# Stingray.net
KiCad netlist of a schematic drawn in Altium Designer
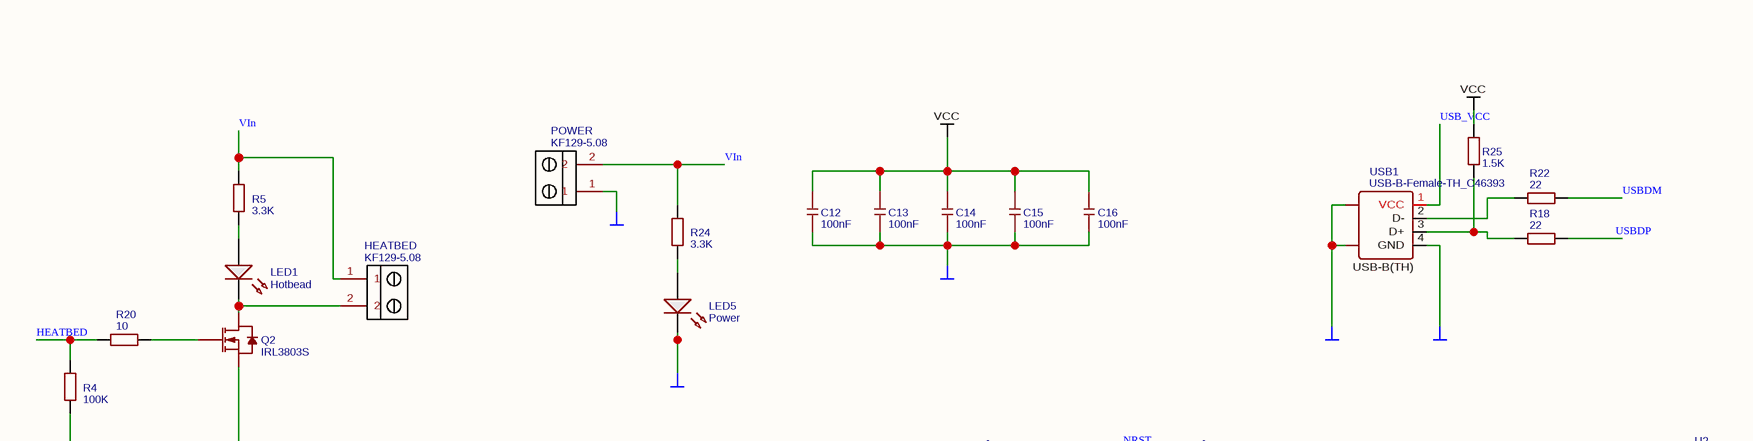
[diagram p0: Stingray.schdoc, top left]
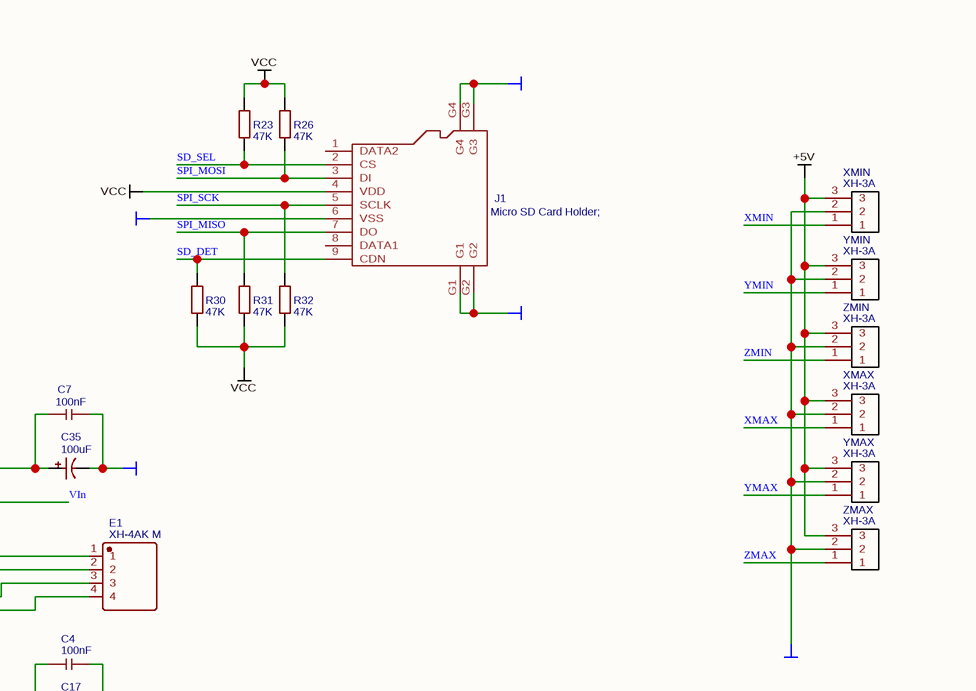
[diagram p1: Stingray.schdoc, top right]
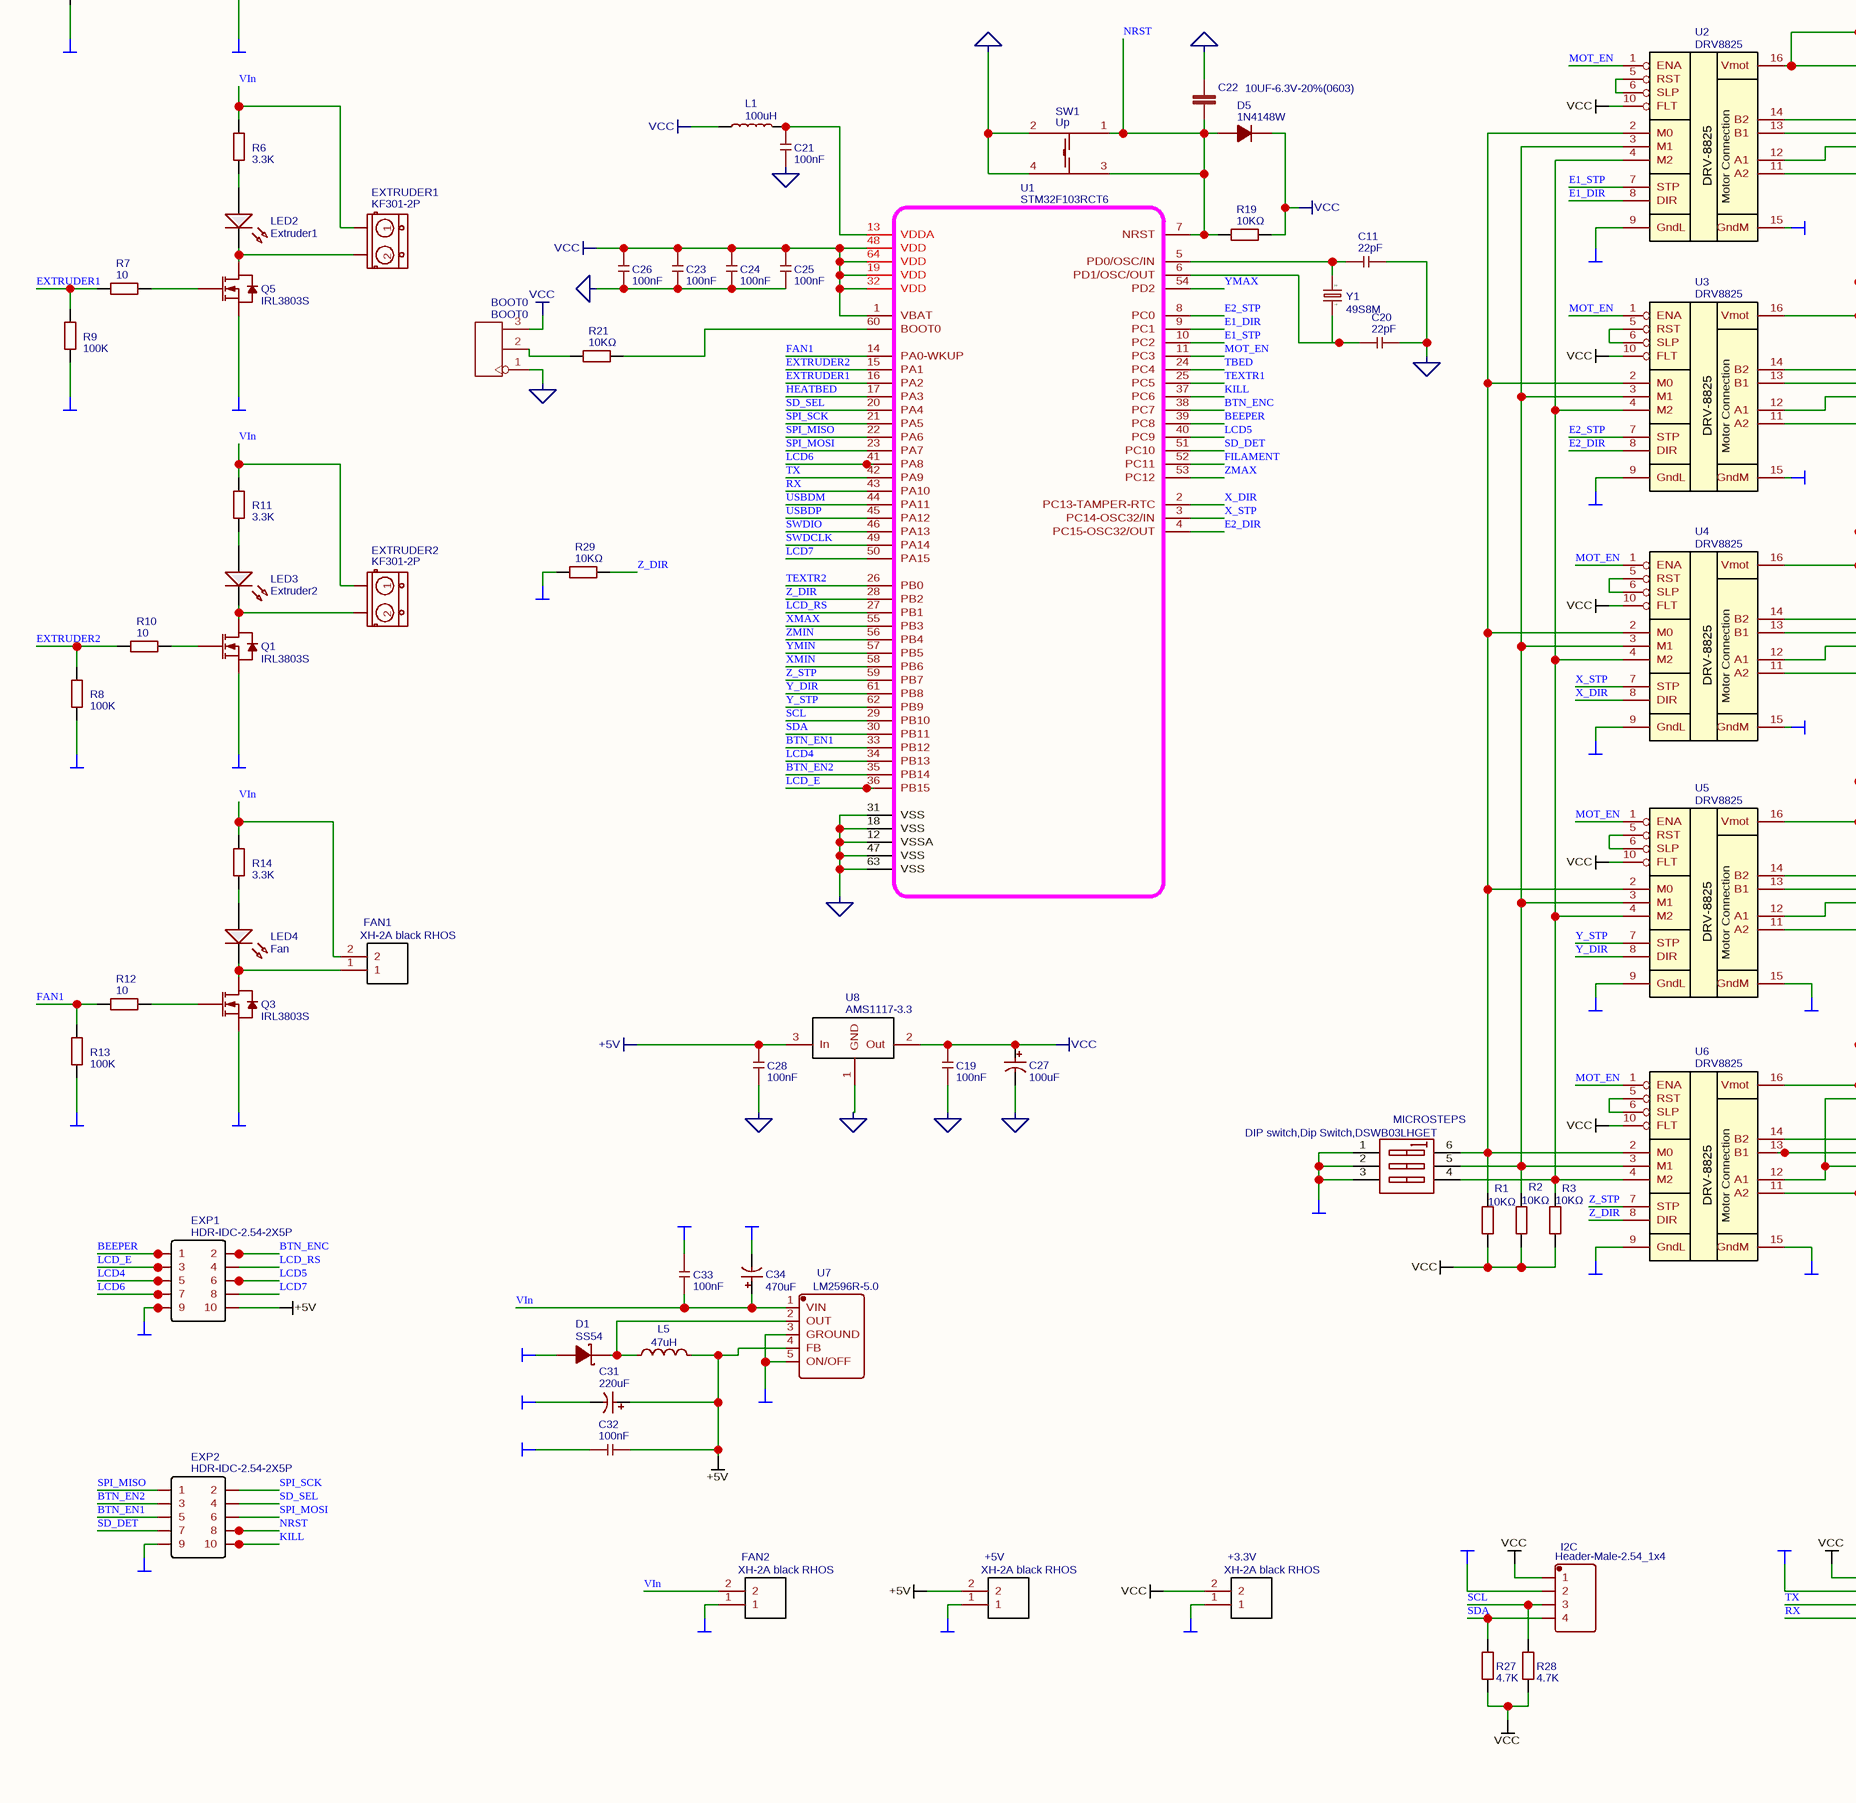
[diagram p2: Stingray.schdoc, bottom left]
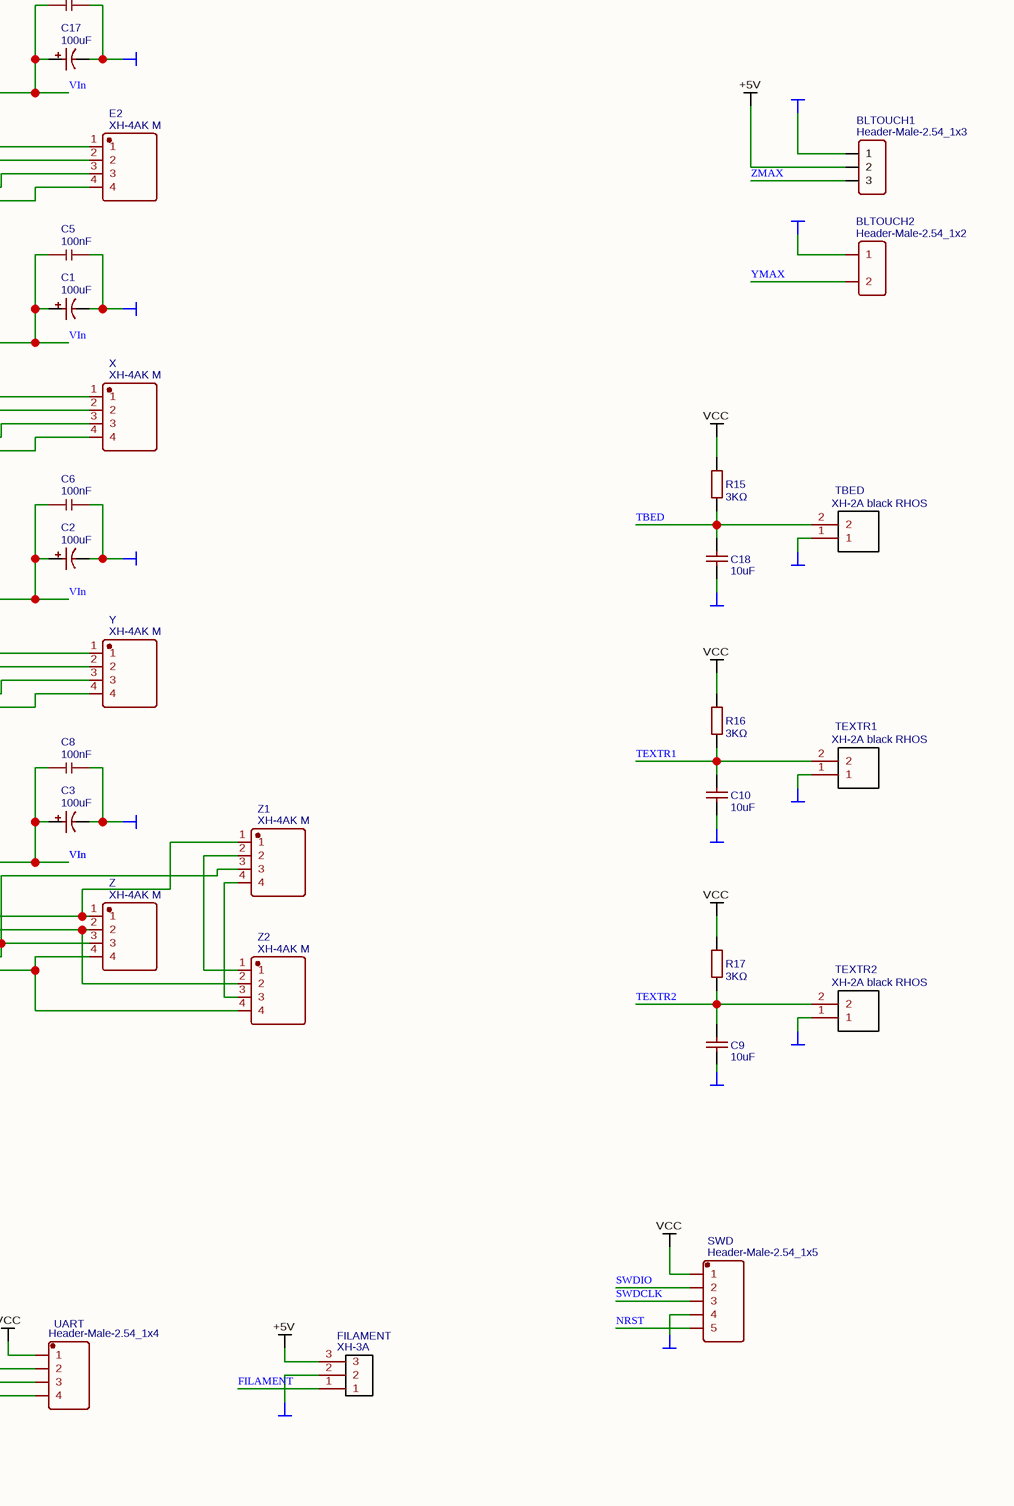
[diagram p3: Stingray.schdoc, bottom right]

(export (version "E")
  (design (tool "Eeschema 10.0.6"))
  (components
    (comp (ref "+3.3V")
      (value "XH-2A black RHOS")
      (fields (field (name "BOM_SUPPLIER PART") "C24193") (field (name "CONTRIBUTOR") "LCSC"))
      (libsource (lib "altium-import") (part "root_2_XH-2A black RHOS_"))
    )
    (comp (ref "+5V")
      (value "XH-2A black RHOS")
      (fields (field (name "BOM_SUPPLIER PART") "C24193") (field (name "CONTRIBUTOR") "LCSC"))
      (libsource (lib "altium-import") (part "root_2_XH-2A black RHOS_"))
    )
    (comp (ref "BLTOUCH1")
      (value "Header-Male-2.54_1x3")
      (fields
        (field (name "BOM_MANUFACTURER PART") "Header2.54mm 1*3P")
        (field (name "BOM_SUPPLIER PART") "C49257")
      )
      (libsource (lib "altium-import") (part "root_0_Header-Male-2.54_1x3_"))
    )
    (comp (ref "BLTOUCH2")
      (value "Header-Male-2.54_1x2")
      (fields (field (name "BOM_MANUFACTURER PART") "826629-2") (field (name "BOM_SUPPLIER PART") "C86471"))
      (libsource (lib "altium-import") (part "root_0_Header-Male-2.54_1x2_"))
    )
    (comp (ref "BOOT0")
      (value "BOOT0")
      (description "DIP-Black-Male-Header-VERT-3P")
      (fields (field (name "BOM_MANUFACTURER PART") "?"))
      (libsource (lib "altium-import") (part "root_2_BOOT0_"))
    )
    (comp (ref "C1")
      (value "100uF")
      (fields
        (field (name "BOM_MANUFACTURER PART") "UT1V101M0607VG")
        (field (name "BOM_SUPPLIER PART") "C82002")
      )
      (libsource (lib "altium-import") (part "root_0_100uF_"))
    )
    (comp (ref "C2")
      (value "100uF")
      (fields
        (field (name "BOM_MANUFACTURER PART") "UT1V101M0607VG")
        (field (name "BOM_SUPPLIER PART") "C82002")
      )
      (libsource (lib "altium-import") (part "root_0_100uF_"))
    )
    (comp (ref "C3")
      (value "100uF")
      (fields
        (field (name "BOM_MANUFACTURER PART") "UT1V101M0607VG")
        (field (name "BOM_SUPPLIER PART") "C82002")
      )
      (libsource (lib "altium-import") (part "root_0_100uF_"))
    )
    (comp (ref "C4")
      (value "100nF")
      (description "SMD CAP Ceramic 100nF-50V-10%-X7R")
      (fields
        (field (name "BOM_MANUFACTURER PART") "0603B104K500NT")
        (field (name "BOM_SUPPLIER PART") "C30926")
      )
      (libsource (lib "altium-import") (part "root_0_100nF_"))
    )
    (comp (ref "C5")
      (value "100nF")
      (description "SMD CAP Ceramic 100nF-50V-10%-X7R")
      (fields
        (field (name "BOM_MANUFACTURER PART") "0603B104K500NT")
        (field (name "BOM_SUPPLIER PART") "C30926")
      )
      (libsource (lib "altium-import") (part "root_0_100nF_"))
    )
    (comp (ref "C6")
      (value "100nF")
      (description "SMD CAP Ceramic 100nF-50V-10%-X7R")
      (fields
        (field (name "BOM_MANUFACTURER PART") "0603B104K500NT")
        (field (name "BOM_SUPPLIER PART") "C30926")
      )
      (libsource (lib "altium-import") (part "root_0_100nF_"))
    )
    (comp (ref "C7")
      (value "100nF")
      (description "SMD CAP Ceramic 100nF-50V-10%-X7R")
      (fields
        (field (name "BOM_MANUFACTURER PART") "0603B104K500NT")
        (field (name "BOM_SUPPLIER PART") "C30926")
      )
      (libsource (lib "altium-import") (part "root_0_100nF_"))
    )
    (comp (ref "C8")
      (value "100nF")
      (description "SMD CAP Ceramic 100nF-50V-10%-X7R")
      (fields
        (field (name "BOM_MANUFACTURER PART") "0603B104K500NT")
        (field (name "BOM_SUPPLIER PART") "C30926")
      )
      (libsource (lib "altium-import") (part "root_0_100nF_"))
    )
    (comp (ref "C9")
      (value "10uF")
      (fields
        (field (name "BOM_MANUFACTURER PART") "CL10A106MO8NQNC")
        (field (name "BOM_SUPPLIER PART") "C92487")
      )
      (libsource (lib "altium-import") (part "root_1_10uF_"))
    )
    (comp (ref "C10")
      (value "10uF")
      (fields
        (field (name "BOM_MANUFACTURER PART") "CL10A106MO8NQNC")
        (field (name "BOM_SUPPLIER PART") "C92487")
      )
      (libsource (lib "altium-import") (part "root_1_10uF_"))
    )
    (comp (ref "C11")
      (value "22pF")
      (description "SMD CAP Ceramic 15pF-50V-5%-NPO;0603")
      (fields (field (name "BOM_MANUFACTURER PART") "CC0603JRNPO9BN150"))
      (libsource (lib "altium-import") (part "root_0_22pF_"))
    )
    (comp (ref "C12")
      (value "100nF")
      (description "SMD CAP Ceramic 100nF-50V-10%-X7R")
      (fields
        (field (name "BOM_MANUFACTURER PART") "0603B104K500NT")
        (field (name "BOM_SUPPLIER PART") "C30926")
      )
      (libsource (lib "altium-import") (part "root_3_100nF_"))
    )
    (comp (ref "C13")
      (value "100nF")
      (description "SMD CAP Ceramic 100nF-50V-10%-X7R")
      (fields
        (field (name "BOM_MANUFACTURER PART") "0603B104K500NT")
        (field (name "BOM_SUPPLIER PART") "C30926")
      )
      (libsource (lib "altium-import") (part "root_3_100nF_"))
    )
    (comp (ref "C14")
      (value "100nF")
      (description "SMD CAP Ceramic 100nF-50V-10%-X7R")
      (fields
        (field (name "BOM_MANUFACTURER PART") "0603B104K500NT")
        (field (name "BOM_SUPPLIER PART") "C30926")
      )
      (libsource (lib "altium-import") (part "root_3_100nF_"))
    )
    (comp (ref "C15")
      (value "100nF")
      (description "SMD CAP Ceramic 100nF-50V-10%-X7R")
      (fields
        (field (name "BOM_MANUFACTURER PART") "0603B104K500NT")
        (field (name "BOM_SUPPLIER PART") "C30926")
      )
      (libsource (lib "altium-import") (part "root_3_100nF_"))
    )
    (comp (ref "C16")
      (value "100nF")
      (description "SMD CAP Ceramic 100nF-50V-10%-X7R")
      (fields
        (field (name "BOM_MANUFACTURER PART") "0603B104K500NT")
        (field (name "BOM_SUPPLIER PART") "C30926")
      )
      (libsource (lib "altium-import") (part "root_3_100nF_"))
    )
    (comp (ref "C17")
      (value "100uF")
      (fields
        (field (name "BOM_MANUFACTURER PART") "UT1V101M0607VG")
        (field (name "BOM_SUPPLIER PART") "C82002")
      )
      (libsource (lib "altium-import") (part "root_0_100uF_"))
    )
    (comp (ref "C18")
      (value "10uF")
      (fields
        (field (name "BOM_MANUFACTURER PART") "CL10A106MO8NQNC")
        (field (name "BOM_SUPPLIER PART") "C92487")
      )
      (libsource (lib "altium-import") (part "root_1_10uF_"))
    )
    (comp (ref "C19")
      (value "100nF")
      (description "SMD CAP Ceramic 100nF-50V-10%-X7R")
      (fields (field (name "BOM_MANUFACTURER PART") "CC0603KRX7R9BB104"))
      (libsource (lib "altium-import") (part "root_1_100nF_"))
    )
    (comp (ref "C20")
      (value "22pF")
      (description "SMD CAP Ceramic 15pF-50V-5%-NPO;0603")
      (fields (field (name "BOM_MANUFACTURER PART") "CC0603JRNPO9BN150"))
      (libsource (lib "altium-import") (part "root_0_22pF_"))
    )
    (comp (ref "C21")
      (value "100nF")
      (description "SMD CAP Ceramic 100nF-50V-10%-X7R")
      (fields (field (name "BOM_MANUFACTURER PART") "CC0603KRX7R9BB104"))
      (libsource (lib "altium-import") (part "root_3_100nF_"))
    )
    (comp (ref "C22")
      (value "10UF-6.3V-20%(0603)")
      (fields (field (name "BOM_MANUFACTURER PART") "?") (field (name "CONTRIBUTOR") "SparkFun"))
      (libsource (lib "altium-import") (part "root_0_10UF-6.3V-20%(0603)_"))
    )
    (comp (ref "C23")
      (value "100nF")
      (description "SMD CAP Ceramic 100nF-50V-10%-X7R")
      (fields (field (name "BOM_MANUFACTURER PART") "CC0603KRX7R9BB104"))
      (libsource (lib "altium-import") (part "root_3_100nF_"))
    )
    (comp (ref "C24")
      (value "100nF")
      (description "SMD CAP Ceramic 100nF-50V-10%-X7R")
      (fields (field (name "BOM_MANUFACTURER PART") "CC0603KRX7R9BB104"))
      (libsource (lib "altium-import") (part "root_3_100nF_"))
    )
    (comp (ref "C25")
      (value "100nF")
      (description "SMD CAP Ceramic 100nF-50V-10%-X7R")
      (fields (field (name "BOM_MANUFACTURER PART") "CC0603KRX7R9BB104"))
      (libsource (lib "altium-import") (part "root_3_100nF_"))
    )
    (comp (ref "C26")
      (value "100nF")
      (description "SMD CAP Ceramic 100nF-50V-10%-X7R")
      (fields (field (name "BOM_MANUFACTURER PART") "CC0603KRX7R9BB104"))
      (libsource (lib "altium-import") (part "root_3_100nF_"))
    )
    (comp (ref "C27")
      (value "100uF")
      (fields
        (field (name "BOM_MANUFACTURER PART") "MV101M6R3E055A")
        (field (name "BOM_SUPPLIER PART") "C65207")
      )
      (libsource (lib "altium-import") (part "root_3_100uF_"))
    )
    (comp (ref "C28")
      (value "100nF")
      (description "SMD CAP Ceramic 100nF-50V-10%-X7R")
      (fields (field (name "BOM_MANUFACTURER PART") "CC0603KRX7R9BB104"))
      (libsource (lib "altium-import") (part "root_3_100nF_"))
    )
    (comp (ref "C31")
      (value "220uF")
      (fields
        (field (name "BOM_MANUFACTURER PART") "UT1A221M0605VG")
        (field (name "BOM_SUPPLIER PART") "C81994")
      )
      (libsource (lib "altium-import") (part "root_2_220uF_"))
    )
    (comp (ref "C32")
      (value "100nF")
      (description "SMD CAP Ceramic 100nF-50V-10%-X7R")
      (fields (field (name "BOM_MANUFACTURER PART") "CC0603KRX7R9BB104"))
      (libsource (lib "altium-import") (part "root_2_100nF_"))
    )
    (comp (ref "C33")
      (value "100nF")
      (description "SMD CAP Ceramic 100nF-50V-10%-X7R")
      (fields (field (name "BOM_MANUFACTURER PART") "CC0603KRX7R9BB104"))
      (libsource (lib "altium-import") (part "root_3_100nF_"))
    )
    (comp (ref "C34")
      (value "470uF")
      (fields
        (field (name "BOM_MANUFACTURER PART") "RVT1V681M1213")
        (field (name "BOM_SUPPLIER PART") "C98216")
      )
      (libsource (lib "altium-import") (part "root_1_470uF_"))
    )
    (comp (ref "C35")
      (value "100uF")
      (fields
        (field (name "BOM_MANUFACTURER PART") "UT1V101M0607VG")
        (field (name "BOM_SUPPLIER PART") "C82002")
      )
      (libsource (lib "altium-import") (part "root_0_100uF_"))
    )
    (comp (ref "D1")
      (value "SS54")
      (fields (field (name "BOM_SUPPLIER PART") "C32513"))
      (libsource (lib "altium-import") (part "root_0_SS54_"))
    )
    (comp (ref "D5")
      (value "1N4148W")
      (fields (field (name "BOM_SUPPLIER PART") "C89641"))
      (libsource (lib "altium-import") (part "root_0_1N4148W_"))
    )
    (comp (ref "E1")
      (value "XH-4AK M")
      (fields (field (name "BOM_SUPPLIER PART") "C146106") (field (name "CONTRIBUTOR") "LCSC"))
      (libsource (lib "altium-import") (part "root_0_XH-4AK M_"))
    )
    (comp (ref "E2")
      (value "XH-4AK M")
      (fields (field (name "BOM_SUPPLIER PART") "C146106") (field (name "CONTRIBUTOR") "LCSC"))
      (libsource (lib "altium-import") (part "root_0_XH-4AK M_"))
    )
    (comp (ref "EXP1")
      (value "HDR-IDC-2.54-2X5P")
      (fields
        (field (name "BOM_MANUFACTURER PART") "IDC Box 2.54mm 2X5P")
        (field (name "BOM_SUPPLIER PART") "C5665")
      )
      (libsource (lib "altium-import") (part "root_0_HDR-IDC-2.54-2X5P_"))
    )
    (comp (ref "EXP2")
      (value "HDR-IDC-2.54-2X5P")
      (fields
        (field (name "BOM_MANUFACTURER PART") "IDC Box 2.54mm 2X5P")
        (field (name "BOM_SUPPLIER PART") "C5665")
      )
      (libsource (lib "altium-import") (part "root_0_HDR-IDC-2.54-2X5P_"))
    )
    (comp (ref "EXTRUDER1")
      (value "KF301-2P")
      (fields (field (name "BOM_MANUFACTURER PART") "?") (field (name "CONTRIBUTOR") "vonk0031"))
      (libsource (lib "altium-import") (part "root_3_KF301-2P_"))
    )
    (comp (ref "EXTRUDER2")
      (value "KF301-2P")
      (fields (field (name "BOM_MANUFACTURER PART") "?") (field (name "CONTRIBUTOR") "vonk0031"))
      (libsource (lib "altium-import") (part "root_3_KF301-2P_"))
    )
    (comp (ref "FAN1")
      (value "XH-2A black RHOS")
      (fields (field (name "BOM_SUPPLIER PART") "C24193") (field (name "CONTRIBUTOR") "LCSC"))
      (libsource (lib "altium-import") (part "root_2_XH-2A black RHOS_"))
    )
    (comp (ref "FAN2")
      (value "XH-2A black RHOS")
      (fields (field (name "BOM_SUPPLIER PART") "C24193") (field (name "CONTRIBUTOR") "LCSC"))
      (libsource (lib "altium-import") (part "root_2_XH-2A black RHOS_"))
    )
    (comp (ref "FILAMENT")
      (value "XH-3A")
      (fields (field (name "BOM_SUPPLIER PART") "C2316") (field (name "CONTRIBUTOR") "LCSC"))
      (libsource (lib "altium-import") (part "root_2_XH-3A_"))
    )
    (comp (ref "HEATBED")
      (value "KF129-5.08")
      (fields (field (name "CONTRIBUTOR") "mmaygli"))
      (libsource (lib "altium-import") (part "root_0_KF129-5.08_"))
    )
    (comp (ref "I2C")
      (value "Header-Male-2.54_1x4")
      (fields
        (field (name "BOM_MANUFACTURER PART") "210S-1*4P L=11.6MMGold-plated black")
        (field (name "BOM_SUPPLIER PART") "C124378")
        (field (name "CONTRIBUTOR") "LCSC")
      )
      (libsource (lib "altium-import") (part "root_0_Header-Male-2.54_1x4_"))
    )
    (comp (ref "J1")
      (value "Micro SD Card Holder;")
      (fields (field (name "BOM_MANUFACTURER PART") "?"))
      (libsource (lib "altium-import") (part "root_0_Micro SD Card Holder;_"))
    )
    (comp (ref "L1")
      (value "100uH")
      (fields
        (field (name "TOLERANCE") "±10%")
        (field (name "BOM_MANUFACTURER PART") "LGA0410-102KP52E")
        (field (name "BOM_SUPPLIER PART") "C72360")
      )
      (libsource (lib "altium-import") (part "root_0_100uH_"))
    )
    (comp (ref "L5")
      (value "47uH")
      (fields
        (field (name "BOM_SUPPLIER PART") "C253613")
        (field (name "BOM_MANUFACTURER PART") "ABG10A50M470")
        (field (name "CONTRIBUTOR") "LCSC")
      )
      (libsource (lib "altium-import") (part "root_0_47uH_"))
    )
    (comp (ref "LED1")
      (value "Hotbead")
      (fields
        (field (name "BOM_MANUFACTURER PART") "17-21/GHC-YR1S2/3T")
        (field (name "BOM_SUPPLIER PART") "E73546")
      )
      (libsource (lib "altium-import") (part "root_3_Hotbead_"))
    )
    (comp (ref "LED2")
      (value "Extruder1")
      (fields
        (field (name "BOM_MANUFACTURER PART") "17-21/GHC-YR1S2/3T")
        (field (name "BOM_SUPPLIER PART") "E73546")
      )
      (libsource (lib "altium-import") (part "root_3_Extruder1_"))
    )
    (comp (ref "LED3")
      (value "Extruder2")
      (fields
        (field (name "BOM_MANUFACTURER PART") "17-21/GHC-YR1S2/3T")
        (field (name "BOM_SUPPLIER PART") "E73546")
      )
      (libsource (lib "altium-import") (part "root_3_Extruder2_"))
    )
    (comp (ref "LED4")
      (value "Fan")
      (fields
        (field (name "BOM_MANUFACTURER PART") "17-21/GHC-YR1S2/3T")
        (field (name "BOM_SUPPLIER PART") "E73546")
      )
      (libsource (lib "altium-import") (part "root_3_Fan_"))
    )
    (comp (ref "LED5")
      (value "Power")
      (fields
        (field (name "BOM_MANUFACTURER PART") "17-21/GHC-YR1S2/3T")
        (field (name "BOM_SUPPLIER PART") "E73546")
      )
      (libsource (lib "altium-import") (part "root_3_Power_"))
    )
    (comp (ref "MICROSTEPS")
      (value "DIP switch,Dip Switch,DSWB03LHGET")
      (fields (field (name "BOM_SUPPLIER PART") "C99420") (field (name "CONTRIBUTOR") "LCSC"))
      (libsource (lib "altium-import") (part "root_0_DIP switch,Dip Switch,DSWB03LHGET_"))
    )
    (comp (ref "POWER")
      (value "KF129-5.08")
      (fields (field (name "CONTRIBUTOR") "mmaygli"))
      (libsource (lib "altium-import") (part "root_2_KF129-5.08_"))
    )
    (comp (ref "Q1")
      (value "IRL3803S")
      (fields (field (name "BOM_SUPPLIER PART") "C2669"))
      (libsource (lib "altium-import") (part "root_0_IRL3803S_"))
    )
    (comp (ref "Q2")
      (value "IRL3803S")
      (fields (field (name "BOM_SUPPLIER PART") "C2669"))
      (libsource (lib "altium-import") (part "root_0_IRL3803S_"))
    )
    (comp (ref "Q3")
      (value "IRL3803S")
      (fields (field (name "BOM_SUPPLIER PART") "C2669"))
      (libsource (lib "altium-import") (part "root_0_IRL3803S_"))
    )
    (comp (ref "Q5")
      (value "IRL3803S")
      (fields (field (name "BOM_SUPPLIER PART") "C2669"))
      (libsource (lib "altium-import") (part "root_0_IRL3803S_"))
    )
    (comp (ref "R1")
      (value "10KΩ")
      (fields
        (field (name "POWER") "1/10W")
        (field (name "TOLERANCE") "±1%")
        (field (name "BOM_MANUFACTURER PART") "0603WAF1002T5E")
      )
      (libsource (lib "altium-import") (part "root_3_10KΩ_"))
    )
    (comp (ref "R2")
      (value "10KΩ")
      (fields
        (field (name "POWER") "1/10W")
        (field (name "TOLERANCE") "±1%")
        (field (name "BOM_MANUFACTURER PART") "0603WAF1002T5E")
      )
      (libsource (lib "altium-import") (part "root_3_10KΩ_"))
    )
    (comp (ref "R3")
      (value "10KΩ")
      (fields
        (field (name "POWER") "1/10W")
        (field (name "TOLERANCE") "±1%")
        (field (name "BOM_MANUFACTURER PART") "0603WAF1002T5E")
      )
      (libsource (lib "altium-import") (part "root_3_10KΩ_"))
    )
    (comp (ref "R4")
      (value "100K")
      (fields
        (field (name "POWER") "1/10W")
        (field (name "TOLERANCE") "±1%")
        (field (name "BOM_MANUFACTURER PART") "0603WAF1002T5E")
      )
      (libsource (lib "altium-import") (part "root_3_100K_"))
    )
    (comp (ref "R5")
      (value "3.3K")
      (fields
        (field (name "POWER") "1/10W")
        (field (name "TOLERANCE") "±1%")
        (field (name "BOM_MANUFACTURER PART") "0603WAF1002T5E")
      )
      (libsource (lib "altium-import") (part "root_3_3.3K_"))
    )
    (comp (ref "R6")
      (value "3.3K")
      (fields
        (field (name "POWER") "1/10W")
        (field (name "TOLERANCE") "±1%")
        (field (name "BOM_MANUFACTURER PART") "0603WAF1002T5E")
      )
      (libsource (lib "altium-import") (part "root_3_3.3K_"))
    )
    (comp (ref "R7")
      (value "10")
      (fields
        (field (name "POWER") "1/10W")
        (field (name "TOLERANCE") "±1%")
        (field (name "BOM_MANUFACTURER PART") "0603WAF1002T5E")
      )
      (libsource (lib "altium-import") (part "root_2_10_"))
    )
    (comp (ref "R8")
      (value "100K")
      (fields
        (field (name "POWER") "1/10W")
        (field (name "TOLERANCE") "±1%")
        (field (name "BOM_MANUFACTURER PART") "0603WAF1002T5E")
      )
      (libsource (lib "altium-import") (part "root_3_100K_"))
    )
    (comp (ref "R9")
      (value "100K")
      (fields
        (field (name "POWER") "1/10W")
        (field (name "TOLERANCE") "±1%")
        (field (name "BOM_MANUFACTURER PART") "0603WAF1002T5E")
      )
      (libsource (lib "altium-import") (part "root_3_100K_"))
    )
    (comp (ref "R10")
      (value "10")
      (fields
        (field (name "POWER") "1/10W")
        (field (name "TOLERANCE") "±1%")
        (field (name "BOM_MANUFACTURER PART") "0603WAF1002T5E")
      )
      (libsource (lib "altium-import") (part "root_2_10_"))
    )
    (comp (ref "R11")
      (value "3.3K")
      (fields
        (field (name "POWER") "1/10W")
        (field (name "TOLERANCE") "±1%")
        (field (name "BOM_MANUFACTURER PART") "0603WAF1002T5E")
      )
      (libsource (lib "altium-import") (part "root_3_3.3K_"))
    )
    (comp (ref "R12")
      (value "10")
      (fields
        (field (name "POWER") "1/10W")
        (field (name "TOLERANCE") "±1%")
        (field (name "BOM_MANUFACTURER PART") "0603WAF1002T5E")
      )
      (libsource (lib "altium-import") (part "root_2_10_"))
    )
    (comp (ref "R13")
      (value "100K")
      (fields
        (field (name "POWER") "1/10W")
        (field (name "TOLERANCE") "±1%")
        (field (name "BOM_MANUFACTURER PART") "0603WAF1002T5E")
      )
      (libsource (lib "altium-import") (part "root_3_100K_"))
    )
    (comp (ref "R14")
      (value "3.3K")
      (fields
        (field (name "POWER") "1/10W")
        (field (name "TOLERANCE") "±1%")
        (field (name "BOM_MANUFACTURER PART") "0603WAF1002T5E")
      )
      (libsource (lib "altium-import") (part "root_3_3.3K_"))
    )
    (comp (ref "R15")
      (value "3KΩ")
      (fields
        (field (name "BOM_MANUFACTURER PART") "RK73B1JTTD302J")
        (field (name "BOM_SUPPLIER PART") "C131708")
        (field (name "CONTRIBUTOR") "LCSC")
      )
      (libsource (lib "altium-import") (part "root_1_3KΩ_"))
    )
    (comp (ref "R16")
      (value "3KΩ")
      (fields
        (field (name "BOM_MANUFACTURER PART") "RK73B1JTTD302J")
        (field (name "BOM_SUPPLIER PART") "C131708")
        (field (name "CONTRIBUTOR") "LCSC")
      )
      (libsource (lib "altium-import") (part "root_1_3KΩ_"))
    )
    (comp (ref "R17")
      (value "3KΩ")
      (fields
        (field (name "BOM_MANUFACTURER PART") "RK73B1JTTD302J")
        (field (name "BOM_SUPPLIER PART") "C131708")
        (field (name "CONTRIBUTOR") "LCSC")
      )
      (libsource (lib "altium-import") (part "root_1_3KΩ_"))
    )
    (comp (ref "R18")
      (value "22")
      (fields
        (field (name "POWER") "1/10W")
        (field (name "TOLERANCE") "±1%")
        (field (name "BOM_MANUFACTURER PART") "0603WAF1002T5E")
      )
      (libsource (lib "altium-import") (part "root_2_22_"))
    )
    (comp (ref "R19")
      (value "10KΩ")
      (fields
        (field (name "POWER") "1/10W")
        (field (name "TOLERANCE") "±1%")
        (field (name "BOM_MANUFACTURER PART") "0603WAF1002T5E")
      )
      (libsource (lib "altium-import") (part "root_0_10KΩ_"))
    )
    (comp (ref "R20")
      (value "10")
      (fields
        (field (name "POWER") "1/10W")
        (field (name "TOLERANCE") "±1%")
        (field (name "BOM_MANUFACTURER PART") "0603WAF1002T5E")
      )
      (libsource (lib "altium-import") (part "root_2_10_"))
    )
    (comp (ref "R21")
      (value "10KΩ")
      (fields
        (field (name "POWER") "1/10W")
        (field (name "TOLERANCE") "±1%")
        (field (name "BOM_MANUFACTURER PART") "0603WAF1002T5E")
      )
      (libsource (lib "altium-import") (part "root_2_10KΩ_"))
    )
    (comp (ref "R22")
      (value "22")
      (fields
        (field (name "POWER") "1/10W")
        (field (name "TOLERANCE") "±1%")
        (field (name "BOM_MANUFACTURER PART") "0603WAF1002T5E")
      )
      (libsource (lib "altium-import") (part "root_2_22_"))
    )
    (comp (ref "R23")
      (value "47K")
      (fields
        (field (name "POWER") "1/10W")
        (field (name "TOLERANCE") "±1%")
        (field (name "BOM_MANUFACTURER PART") "0603WAF1002T5E")
      )
      (libsource (lib "altium-import") (part "root_3_47K_"))
    )
    (comp (ref "R24")
      (value "3.3K")
      (fields
        (field (name "POWER") "1/10W")
        (field (name "TOLERANCE") "±1%")
        (field (name "BOM_MANUFACTURER PART") "0603WAF1002T5E")
      )
      (libsource (lib "altium-import") (part "root_3_3.3K_"))
    )
    (comp (ref "R25")
      (value "1.5K")
      (fields
        (field (name "POWER") "1/10W")
        (field (name "TOLERANCE") "±1%")
        (field (name "BOM_MANUFACTURER PART") "0603WAF1002T5E")
      )
      (libsource (lib "altium-import") (part "root_3_1.5K_"))
    )
    (comp (ref "R26")
      (value "47K")
      (fields
        (field (name "POWER") "1/10W")
        (field (name "TOLERANCE") "±1%")
        (field (name "BOM_MANUFACTURER PART") "0603WAF1002T5E")
      )
      (libsource (lib "altium-import") (part "root_3_47K_"))
    )
    (comp (ref "R27")
      (value "4.7K")
      (fields
        (field (name "POWER") "1/10W")
        (field (name "TOLERANCE") "±1%")
        (field (name "BOM_MANUFACTURER PART") "0603WAF1002T5E")
      )
      (libsource (lib "altium-import") (part "root_3_4.7K_"))
    )
    (comp (ref "R28")
      (value "4.7K")
      (fields
        (field (name "POWER") "1/10W")
        (field (name "TOLERANCE") "±1%")
        (field (name "BOM_MANUFACTURER PART") "0603WAF1002T5E")
      )
      (libsource (lib "altium-import") (part "root_3_4.7K_"))
    )
    (comp (ref "R29")
      (value "10KΩ")
      (fields
        (field (name "POWER") "1/10W")
        (field (name "TOLERANCE") "±1%")
        (field (name "BOM_MANUFACTURER PART") "0603WAF1002T5E")
      )
      (libsource (lib "altium-import") (part "root_2_10KΩ_"))
    )
    (comp (ref "R30")
      (value "47K")
      (fields
        (field (name "POWER") "1/10W")
        (field (name "TOLERANCE") "±1%")
        (field (name "BOM_MANUFACTURER PART") "0603WAF1002T5E")
      )
      (libsource (lib "altium-import") (part "root_3_47K_"))
    )
    (comp (ref "R31")
      (value "47K")
      (fields
        (field (name "POWER") "1/10W")
        (field (name "TOLERANCE") "±1%")
        (field (name "BOM_MANUFACTURER PART") "0603WAF1002T5E")
      )
      (libsource (lib "altium-import") (part "root_3_47K_"))
    )
    (comp (ref "R32")
      (value "47K")
      (fields
        (field (name "POWER") "1/10W")
        (field (name "TOLERANCE") "±1%")
        (field (name "BOM_MANUFACTURER PART") "0603WAF1002T5E")
      )
      (libsource (lib "altium-import") (part "root_3_47K_"))
    )
    (comp (ref "SW1")
      (value "Up")
      (fields
        (field (name "BOM_MANUFACTURER PART") "Switch,6*6*5Plastic head,260G, 0.25mm,DIP2")
        (field (name "BOM_SUPPLIER PART") "C71845")
        (field (name "CONTRIBUTOR") "LCSC")
      )
      (libsource (lib "altium-import") (part "root_0_Up_"))
    )
    (comp (ref "SWD")
      (value "Header-Male-2.54_1x5")
      (fields
        (field (name "BOM_MANUFACTURER PART") "210S-1*5P L=11.6MMGold-plated black")
        (field (name "BOM_SUPPLIER PART") "C124379")
        (field (name "CONTRIBUTOR") "LCSC")
      )
      (libsource (lib "altium-import") (part "root_0_Header-Male-2.54_1x5_"))
    )
    (comp (ref "TBED")
      (value "XH-2A black RHOS")
      (fields (field (name "BOM_SUPPLIER PART") "C24193") (field (name "CONTRIBUTOR") "LCSC"))
      (libsource (lib "altium-import") (part "root_2_XH-2A black RHOS_"))
    )
    (comp (ref "TEXTR1")
      (value "XH-2A black RHOS")
      (fields (field (name "BOM_SUPPLIER PART") "C24193") (field (name "CONTRIBUTOR") "LCSC"))
      (libsource (lib "altium-import") (part "root_2_XH-2A black RHOS_"))
    )
    (comp (ref "TEXTR2")
      (value "XH-2A black RHOS")
      (fields (field (name "BOM_SUPPLIER PART") "C24193") (field (name "CONTRIBUTOR") "LCSC"))
      (libsource (lib "altium-import") (part "root_2_XH-2A black RHOS_"))
    )
    (comp (ref "U1")
      (value "STM32F103RCT6")
      (fields (field (name "BOM_MANUFACTURER PART") "?"))
      (libsource (lib "altium-import") (part "root_0_STM32F103RCT6_"))
    )
    (comp (ref "U2")
      (value "DRV8825")
      (fields (field (name "BOM_SUPPLIER PART") "2133") (field (name "CONTRIBUTOR") "Origami30"))
      (libsource (lib "altium-import") (part "root_0_DRV8825_"))
    )
    (comp (ref "U3")
      (value "DRV8825")
      (fields (field (name "BOM_SUPPLIER PART") "2133") (field (name "CONTRIBUTOR") "Origami30"))
      (libsource (lib "altium-import") (part "root_0_DRV8825_"))
    )
    (comp (ref "U4")
      (value "DRV8825")
      (fields (field (name "BOM_SUPPLIER PART") "2133") (field (name "CONTRIBUTOR") "Origami30"))
      (libsource (lib "altium-import") (part "root_0_DRV8825_"))
    )
    (comp (ref "U5")
      (value "DRV8825")
      (fields (field (name "BOM_SUPPLIER PART") "2133") (field (name "CONTRIBUTOR") "Origami30"))
      (libsource (lib "altium-import") (part "root_0_DRV8825_"))
    )
    (comp (ref "U6")
      (value "DRV8825")
      (fields (field (name "BOM_SUPPLIER PART") "2133") (field (name "CONTRIBUTOR") "Origami30"))
      (libsource (lib "altium-import") (part "root_0_DRV8825_"))
    )
    (comp (ref "U7")
      (value "LM2596R-5.0")
      (fields (field (name "BOM_SUPPLIER PART") "C77782"))
      (libsource (lib "altium-import") (part "root_0_LM2596R-5.0_"))
    )
    (comp (ref "U8")
      (value "AMS1117-3.3")
      (fields (field (name "BOM_SUPPLIER PART") "C6186"))
      (libsource (lib "altium-import") (part "root_0_AMS1117-3.3_"))
    )
    (comp (ref "UART")
      (value "Header-Male-2.54_1x4")
      (fields
        (field (name "BOM_MANUFACTURER PART") "210S-1*4P L=11.6MMGold-plated black")
        (field (name "BOM_SUPPLIER PART") "C124378")
        (field (name "CONTRIBUTOR") "LCSC")
      )
      (libsource (lib "altium-import") (part "root_0_Header-Male-2.54_1x4_"))
    )
    (comp (ref "USB1")
      (value "USB-B-Female-TH_C46393")
      (fields
        (field (name "BOM_MANUFACTURER PART") "USB-B-Female-90-TH")
        (field (name "BOM_SUPPLIER PART") "C46393")
      )
      (libsource (lib "altium-import") (part "root_0_USB-B-Female-TH_C46393_"))
    )
    (comp (ref "X")
      (value "XH-4AK M")
      (fields (field (name "BOM_SUPPLIER PART") "C146106") (field (name "CONTRIBUTOR") "LCSC"))
      (libsource (lib "altium-import") (part "root_0_XH-4AK M_"))
    )
    (comp (ref "XMAX")
      (value "XH-3A")
      (fields (field (name "BOM_SUPPLIER PART") "C2316") (field (name "CONTRIBUTOR") "LCSC"))
      (libsource (lib "altium-import") (part "root_2_XH-3A_"))
    )
    (comp (ref "XMIN")
      (value "XH-3A")
      (fields (field (name "BOM_SUPPLIER PART") "C2316") (field (name "CONTRIBUTOR") "LCSC"))
      (libsource (lib "altium-import") (part "root_2_XH-3A_"))
    )
    (comp (ref "Y")
      (value "XH-4AK M")
      (fields (field (name "BOM_SUPPLIER PART") "C146106") (field (name "CONTRIBUTOR") "LCSC"))
      (libsource (lib "altium-import") (part "root_0_XH-4AK M_"))
    )
    (comp (ref "Y1")
      (value "49S8M")
      (description "DIP Crystal 8MHz-20pF-20ppm-60R;")
      (libsource (lib "altium-import") (part "root_1_49S8M_"))
    )
    (comp (ref "YMAX")
      (value "XH-3A")
      (fields (field (name "BOM_SUPPLIER PART") "C2316") (field (name "CONTRIBUTOR") "LCSC"))
      (libsource (lib "altium-import") (part "root_2_XH-3A_"))
    )
    (comp (ref "YMIN")
      (value "XH-3A")
      (fields (field (name "BOM_SUPPLIER PART") "C2316") (field (name "CONTRIBUTOR") "LCSC"))
      (libsource (lib "altium-import") (part "root_2_XH-3A_"))
    )
    (comp (ref "Z")
      (value "XH-4AK M")
      (fields (field (name "BOM_SUPPLIER PART") "C146106") (field (name "CONTRIBUTOR") "LCSC"))
      (libsource (lib "altium-import") (part "root_0_XH-4AK M_"))
    )
    (comp (ref "Z1")
      (value "XH-4AK M")
      (fields (field (name "BOM_SUPPLIER PART") "C146106") (field (name "CONTRIBUTOR") "LCSC"))
      (libsource (lib "altium-import") (part "root_0_XH-4AK M_"))
    )
    (comp (ref "Z2")
      (value "XH-4AK M")
      (fields (field (name "BOM_SUPPLIER PART") "C146106") (field (name "CONTRIBUTOR") "LCSC"))
      (libsource (lib "altium-import") (part "root_0_XH-4AK M_"))
    )
    (comp (ref "ZMAX")
      (value "XH-3A")
      (fields (field (name "BOM_SUPPLIER PART") "C2316") (field (name "CONTRIBUTOR") "LCSC"))
      (libsource (lib "altium-import") (part "root_2_XH-3A_"))
    )
    (comp (ref "ZMIN")
      (value "XH-3A")
      (fields (field (name "BOM_SUPPLIER PART") "C2316") (field (name "CONTRIBUTOR") "LCSC"))
      (libsource (lib "altium-import") (part "root_2_XH-3A_"))
    )
  )
  (nets
    (net (code "1") (name "+5V") (class "Default")
      (node (ref "+5V") (pin "2") (pinfunction "2_2") (pintype "passive"))
      (node (ref "BLTOUCH1") (pin "2") (pinfunction "2_2") (pintype "passive"))
      (node (ref "C28") (pin "1") (pinfunction "1_1") (pintype "passive"))
      (node (ref "C31") (pin "1") (pinfunction "1_1") (pintype "passive"))
      (node (ref "C32") (pin "1") (pinfunction "1_1") (pintype "passive"))
      (node (ref "EXP1") (pin "10") (pinfunction "10_10") (pintype "passive"))
      (node (ref "FILAMENT") (pin "3") (pinfunction "3_3") (pintype "passive"))
      (node (ref "L5") (pin "2") (pinfunction "2_2") (pintype "passive"))
      (node (ref "U7") (pin "4") (pinfunction "FB_4") (pintype "passive"))
      (node (ref "U8") (pin "3") (pinfunction "In_3") (pintype "passive"))
      (node (ref "XMAX") (pin "3") (pinfunction "3_3") (pintype "passive"))
      (node (ref "XMIN") (pin "3") (pinfunction "3_3") (pintype "passive"))
      (node (ref "YMAX") (pin "3") (pinfunction "3_3") (pintype "passive"))
      (node (ref "YMIN") (pin "3") (pinfunction "3_3") (pintype "passive"))
      (node (ref "ZMAX") (pin "3") (pinfunction "3_3") (pintype "passive"))
      (node (ref "ZMIN") (pin "3") (pinfunction "3_3") (pintype "passive"))
    )
    (net (code "2") (name "/BEEPER") (class "Default")
      (node (ref "EXP1") (pin "1") (pinfunction "1_1") (pintype "passive"))
      (node (ref "U1") (pin "39") (pinfunction "PC8_39") (pintype "passive"))
    )
    (net (code "3") (name "/BTN_EN1") (class "Default")
      (node (ref "EXP2") (pin "5") (pinfunction "5_5") (pintype "passive"))
      (node (ref "U1") (pin "33") (pinfunction "PB12_33") (pintype "passive"))
    )
    (net (code "4") (name "/BTN_EN2") (class "Default")
      (node (ref "EXP2") (pin "3") (pinfunction "3_3") (pintype "passive"))
      (node (ref "U1") (pin "35") (pinfunction "PB14_35") (pintype "passive"))
    )
    (net (code "5") (name "/BTN_ENC") (class "Default")
      (node (ref "EXP1") (pin "2") (pinfunction "2_2") (pintype "passive"))
      (node (ref "U1") (pin "38") (pinfunction "PC7_38") (pintype "passive"))
    )
    (net (code "6") (name "/E1_DIR") (class "Default")
      (node (ref "U1") (pin "9") (pinfunction "PC1_9") (pintype "passive"))
      (node (ref "U2") (pin "8") (pinfunction "DIR_8") (pintype "passive"))
    )
    (net (code "7") (name "/E1_STP") (class "Default")
      (node (ref "U1") (pin "10") (pinfunction "PC2_10") (pintype "passive"))
      (node (ref "U2") (pin "7") (pinfunction "STP_7") (pintype "passive"))
    )
    (net (code "8") (name "/E2_DIR") (class "Default")
      (node (ref "U1") (pin "4") (pinfunction "PC15-OSC32/OUT_4") (pintype "passive"))
      (node (ref "U3") (pin "8") (pinfunction "DIR_8") (pintype "passive"))
    )
    (net (code "9") (name "/E2_STP") (class "Default")
      (node (ref "U1") (pin "8") (pinfunction "PC0_8") (pintype "passive"))
      (node (ref "U3") (pin "7") (pinfunction "STP_7") (pintype "passive"))
    )
    (net (code "10") (name "/EXTRUDER1") (class "Default")
      (node (ref "R7") (pin "2") (pinfunction "2_2") (pintype "passive"))
      (node (ref "R9") (pin "1") (pinfunction "1_1") (pintype "passive"))
      (node (ref "U1") (pin "16") (pinfunction "PA2_16") (pintype "passive"))
    )
    (net (code "11") (name "/EXTRUDER2") (class "Default")
      (node (ref "R10") (pin "2") (pinfunction "2_2") (pintype "passive"))
      (node (ref "R8") (pin "1") (pinfunction "1_1") (pintype "passive"))
      (node (ref "U1") (pin "15") (pinfunction "PA1_15") (pintype "passive"))
    )
    (net (code "12") (name "/FAN1") (class "Default")
      (node (ref "R12") (pin "2") (pinfunction "2_2") (pintype "passive"))
      (node (ref "R13") (pin "1") (pinfunction "1_1") (pintype "passive"))
      (node (ref "U1") (pin "14") (pinfunction "PA0-WKUP_14") (pintype "passive"))
    )
    (net (code "13") (name "/FILAMENT") (class "Default")
      (node (ref "FILAMENT") (pin "1") (pinfunction "1_1") (pintype "passive"))
      (node (ref "U1") (pin "52") (pinfunction "PC11_52") (pintype "passive"))
    )
    (net (code "14") (name "/HEATBED") (class "Default")
      (node (ref "R20") (pin "2") (pinfunction "2_2") (pintype "passive"))
      (node (ref "R4") (pin "1") (pinfunction "1_1") (pintype "passive"))
      (node (ref "U1") (pin "17") (pinfunction "PA3_17") (pintype "passive"))
    )
    (net (code "15") (name "/KILL") (class "Default")
      (node (ref "EXP2") (pin "10") (pinfunction "10_10") (pintype "passive"))
      (node (ref "U1") (pin "37") (pinfunction "PC6_37") (pintype "passive"))
    )
    (net (code "16") (name "/LCD4") (class "Default")
      (node (ref "EXP1") (pin "5") (pinfunction "5_5") (pintype "passive"))
      (node (ref "U1") (pin "34") (pinfunction "PB13_34") (pintype "passive"))
    )
    (net (code "17") (name "/LCD5") (class "Default")
      (node (ref "EXP1") (pin "6") (pinfunction "6_6") (pintype "passive"))
      (node (ref "U1") (pin "40") (pinfunction "PC9_40") (pintype "passive"))
    )
    (net (code "18") (name "/LCD6") (class "Default")
      (node (ref "EXP1") (pin "7") (pinfunction "7_7") (pintype "passive"))
      (node (ref "U1") (pin "41") (pinfunction "PA8_41") (pintype "passive"))
    )
    (net (code "19") (name "/LCD7") (class "Default")
      (node (ref "EXP1") (pin "8") (pinfunction "8_8") (pintype "passive"))
      (node (ref "U1") (pin "50") (pinfunction "PA15_50") (pintype "passive"))
    )
    (net (code "20") (name "/LCD_E") (class "Default")
      (node (ref "EXP1") (pin "3") (pinfunction "3_3") (pintype "passive"))
      (node (ref "U1") (pin "36") (pinfunction "PB15_36") (pintype "passive"))
    )
    (net (code "21") (name "/LCD_RS") (class "Default")
      (node (ref "EXP1") (pin "4") (pinfunction "4_4") (pintype "passive"))
      (node (ref "U1") (pin "27") (pinfunction "PB1_27") (pintype "passive"))
    )
    (net (code "22") (name "/MOT_EN") (class "Default")
      (node (ref "U1") (pin "11") (pinfunction "PC3_11") (pintype "passive"))
      (node (ref "U2") (pin "1") (pinfunction "ENA_1") (pintype "passive"))
      (node (ref "U3") (pin "1") (pinfunction "ENA_1") (pintype "passive"))
      (node (ref "U4") (pin "1") (pinfunction "ENA_1") (pintype "passive"))
      (node (ref "U5") (pin "1") (pinfunction "ENA_1") (pintype "passive"))
      (node (ref "U6") (pin "1") (pinfunction "ENA_1") (pintype "passive"))
    )
    (net (code "23") (name "/NRST") (class "Default")
      (node (ref "C22") (pin "2") (pinfunction "2_2") (pintype "passive"))
      (node (ref "D5") (pin "1") (pinfunction "A_1") (pintype "passive"))
      (node (ref "EXP2") (pin "8") (pinfunction "8_8") (pintype "passive"))
      (node (ref "R19") (pin "1") (pinfunction "1_1") (pintype "passive"))
      (node (ref "SW1") (pin "1") (pinfunction "1_1") (pintype "passive"))
      (node (ref "SW1") (pin "3") (pinfunction "3_3") (pintype "passive"))
      (node (ref "SWD") (pin "5") (pinfunction "5_5") (pintype "passive"))
      (node (ref "U1") (pin "7") (pinfunction "NRST_7") (pintype "passive"))
    )
    (net (code "24") (name "/RX") (class "Default")
      (node (ref "U1") (pin "43") (pinfunction "PA10_43") (pintype "passive"))
      (node (ref "UART") (pin "4") (pinfunction "4_4") (pintype "passive"))
    )
    (net (code "25") (name "/SCL") (class "Default")
      (node (ref "I2C") (pin "3") (pinfunction "3_3") (pintype "passive"))
      (node (ref "R28") (pin "1") (pinfunction "1_1") (pintype "passive"))
      (node (ref "U1") (pin "29") (pinfunction "PB10_29") (pintype "passive"))
    )
    (net (code "26") (name "/SDA") (class "Default")
      (node (ref "I2C") (pin "4") (pinfunction "4_4") (pintype "passive"))
      (node (ref "R27") (pin "1") (pinfunction "1_1") (pintype "passive"))
      (node (ref "U1") (pin "30") (pinfunction "PB11_30") (pintype "passive"))
    )
    (net (code "27") (name "/SD_DET") (class "Default")
      (node (ref "EXP2") (pin "7") (pinfunction "7_7") (pintype "passive"))
      (node (ref "J1") (pin "9") (pinfunction "CDN_9") (pintype "passive"))
      (node (ref "R30") (pin "1") (pinfunction "1_1") (pintype "passive"))
      (node (ref "U1") (pin "51") (pinfunction "PC10_51") (pintype "passive"))
    )
    (net (code "28") (name "/SD_SEL") (class "Default")
      (node (ref "EXP2") (pin "4") (pinfunction "4_4") (pintype "passive"))
      (node (ref "J1") (pin "2") (pinfunction "CS_2") (pintype "passive"))
      (node (ref "R23") (pin "2") (pinfunction "2_2") (pintype "passive"))
      (node (ref "U1") (pin "20") (pinfunction "PA4_20") (pintype "passive"))
    )
    (net (code "29") (name "/SPI_MISO") (class "Default")
      (node (ref "EXP2") (pin "1") (pinfunction "1_1") (pintype "passive"))
      (node (ref "J1") (pin "7") (pinfunction "DO_7") (pintype "passive"))
      (node (ref "R31") (pin "1") (pinfunction "1_1") (pintype "passive"))
      (node (ref "U1") (pin "22") (pinfunction "PA6_22") (pintype "passive"))
    )
    (net (code "30") (name "/SPI_MOSI") (class "Default")
      (node (ref "EXP2") (pin "6") (pinfunction "6_6") (pintype "passive"))
      (node (ref "J1") (pin "3") (pinfunction "DI_3") (pintype "passive"))
      (node (ref "R26") (pin "2") (pinfunction "2_2") (pintype "passive"))
      (node (ref "U1") (pin "23") (pinfunction "PA7_23") (pintype "passive"))
    )
    (net (code "31") (name "/SPI_SCK") (class "Default")
      (node (ref "EXP2") (pin "2") (pinfunction "2_2") (pintype "passive"))
      (node (ref "J1") (pin "5") (pinfunction "SCLK_5") (pintype "passive"))
      (node (ref "R32") (pin "1") (pinfunction "1_1") (pintype "passive"))
      (node (ref "U1") (pin "21") (pinfunction "PA5_21") (pintype "passive"))
    )
    (net (code "32") (name "/SWDCLK") (class "Default")
      (node (ref "SWD") (pin "3") (pinfunction "3_3") (pintype "passive"))
      (node (ref "U1") (pin "49") (pinfunction "PA14_49") (pintype "passive"))
    )
    (net (code "33") (name "/SWDIO") (class "Default")
      (node (ref "SWD") (pin "2") (pinfunction "2_2") (pintype "passive"))
      (node (ref "U1") (pin "46") (pinfunction "PA13_46") (pintype "passive"))
    )
    (net (code "34") (name "/TBED") (class "Default")
      (node (ref "C18") (pin "2") (pinfunction "2_2") (pintype "passive"))
      (node (ref "R15") (pin "1") (pinfunction "1_1") (pintype "passive"))
      (node (ref "TBED") (pin "2") (pinfunction "2_2") (pintype "passive"))
      (node (ref "U1") (pin "24") (pinfunction "PC4_24") (pintype "passive"))
    )
    (net (code "35") (name "/TEXTR1") (class "Default")
      (node (ref "C10") (pin "2") (pinfunction "2_2") (pintype "passive"))
      (node (ref "R16") (pin "1") (pinfunction "1_1") (pintype "passive"))
      (node (ref "TEXTR1") (pin "2") (pinfunction "2_2") (pintype "passive"))
      (node (ref "U1") (pin "25") (pinfunction "PC5_25") (pintype "passive"))
    )
    (net (code "36") (name "/TEXTR2") (class "Default")
      (node (ref "C9") (pin "2") (pinfunction "2_2") (pintype "passive"))
      (node (ref "R17") (pin "1") (pinfunction "1_1") (pintype "passive"))
      (node (ref "TEXTR2") (pin "2") (pinfunction "2_2") (pintype "passive"))
      (node (ref "U1") (pin "26") (pinfunction "PB0_26") (pintype "passive"))
    )
    (net (code "37") (name "/TX") (class "Default")
      (node (ref "U1") (pin "42") (pinfunction "PA9_42") (pintype "passive"))
      (node (ref "UART") (pin "3") (pinfunction "3_3") (pintype "passive"))
    )
    (net (code "38") (name "/USBDM") (class "Default")
      (node (ref "R22") (pin "1") (pinfunction "1_1") (pintype "passive"))
      (node (ref "U1") (pin "44") (pinfunction "PA11_44") (pintype "passive"))
    )
    (net (code "39") (name "/USBDP") (class "Default")
      (node (ref "R18") (pin "1") (pinfunction "1_1") (pintype "passive"))
      (node (ref "U1") (pin "45") (pinfunction "PA12_45") (pintype "passive"))
    )
    (net (code "40") (name "/USB_VCC") (class "Default")
      (node (ref "USB1") (pin "1") (pinfunction "VCC_1") (pintype "passive"))
    )
    (net (code "41") (name "/VIn") (class "Default")
      (node (ref "C1") (pin "1") (pinfunction "1_1") (pintype "passive"))
      (node (ref "C17") (pin "1") (pinfunction "1_1") (pintype "passive"))
      (node (ref "C2") (pin "1") (pinfunction "1_1") (pintype "passive"))
      (node (ref "C3") (pin "1") (pinfunction "1_1") (pintype "passive"))
      (node (ref "C33") (pin "2") (pinfunction "2_2") (pintype "passive"))
      (node (ref "C34") (pin "1") (pinfunction "1_1") (pintype "passive"))
      (node (ref "C35") (pin "1") (pinfunction "1_1") (pintype "passive"))
      (node (ref "C4") (pin "1") (pinfunction "1_1") (pintype "passive"))
      (node (ref "C5") (pin "1") (pinfunction "1_1") (pintype "passive"))
      (node (ref "C6") (pin "1") (pinfunction "1_1") (pintype "passive"))
      (node (ref "C7") (pin "1") (pinfunction "1_1") (pintype "passive"))
      (node (ref "C8") (pin "1") (pinfunction "1_1") (pintype "passive"))
      (node (ref "EXTRUDER1") (pin "1") (pinfunction "1_1") (pintype "passive"))
      (node (ref "EXTRUDER2") (pin "1") (pinfunction "1_1") (pintype "passive"))
      (node (ref "FAN1") (pin "2") (pinfunction "2_2") (pintype "passive"))
      (node (ref "FAN2") (pin "2") (pinfunction "2_2") (pintype "passive"))
      (node (ref "HEATBED") (pin "1") (pinfunction "1_1") (pintype "passive"))
      (node (ref "POWER") (pin "2") (pinfunction "2_2") (pintype "passive"))
      (node (ref "R11") (pin "1") (pinfunction "1_1") (pintype "passive"))
      (node (ref "R14") (pin "1") (pinfunction "1_1") (pintype "passive"))
      (node (ref "R24") (pin "1") (pinfunction "1_1") (pintype "passive"))
      (node (ref "R5") (pin "1") (pinfunction "1_1") (pintype "passive"))
      (node (ref "R6") (pin "1") (pinfunction "1_1") (pintype "passive"))
      (node (ref "U2") (pin "16") (pinfunction "Vmot_16") (pintype "passive"))
      (node (ref "U3") (pin "16") (pinfunction "Vmot_16") (pintype "passive"))
      (node (ref "U4") (pin "16") (pinfunction "Vmot_16") (pintype "passive"))
      (node (ref "U5") (pin "16") (pinfunction "Vmot_16") (pintype "passive"))
      (node (ref "U6") (pin "16") (pinfunction "Vmot_16") (pintype "passive"))
      (node (ref "U7") (pin "1") (pinfunction "VIN_1") (pintype "passive"))
    )
    (net (code "42") (name "/XMAX") (class "Default")
      (node (ref "U1") (pin "55") (pinfunction "PB3_55") (pintype "passive"))
      (node (ref "XMAX") (pin "1") (pinfunction "1_1") (pintype "passive"))
    )
    (net (code "43") (name "/XMIN") (class "Default")
      (node (ref "U1") (pin "58") (pinfunction "PB6_58") (pintype "passive"))
      (node (ref "XMIN") (pin "1") (pinfunction "1_1") (pintype "passive"))
    )
    (net (code "44") (name "/X_DIR") (class "Default")
      (node (ref "U1") (pin "2") (pinfunction "PC13-TAMPER-RTC_2") (pintype "passive"))
      (node (ref "U4") (pin "8") (pinfunction "DIR_8") (pintype "passive"))
    )
    (net (code "45") (name "/X_STP") (class "Default")
      (node (ref "U1") (pin "3") (pinfunction "PC14-OSC32/IN_3") (pintype "passive"))
      (node (ref "U4") (pin "7") (pinfunction "STP_7") (pintype "passive"))
    )
    (net (code "46") (name "/YMAX") (class "Default")
      (node (ref "BLTOUCH2") (pin "2") (pinfunction "2_2") (pintype "passive"))
      (node (ref "U1") (pin "54") (pinfunction "PD2_54") (pintype "passive"))
      (node (ref "YMAX") (pin "1") (pinfunction "1_1") (pintype "passive"))
    )
    (net (code "47") (name "/YMIN") (class "Default")
      (node (ref "U1") (pin "57") (pinfunction "PB5_57") (pintype "passive"))
      (node (ref "YMIN") (pin "1") (pinfunction "1_1") (pintype "passive"))
    )
    (net (code "48") (name "/Y_DIR") (class "Default")
      (node (ref "U1") (pin "61") (pinfunction "PB8_61") (pintype "passive"))
      (node (ref "U5") (pin "8") (pinfunction "DIR_8") (pintype "passive"))
    )
    (net (code "49") (name "/Y_STP") (class "Default")
      (node (ref "U1") (pin "62") (pinfunction "PB9_62") (pintype "passive"))
      (node (ref "U5") (pin "7") (pinfunction "STP_7") (pintype "passive"))
    )
    (net (code "50") (name "/ZMAX") (class "Default")
      (node (ref "BLTOUCH1") (pin "3") (pinfunction "3_3") (pintype "passive"))
      (node (ref "U1") (pin "53") (pinfunction "PC12_53") (pintype "passive"))
      (node (ref "ZMAX") (pin "1") (pinfunction "1_1") (pintype "passive"))
    )
    (net (code "51") (name "/ZMIN") (class "Default")
      (node (ref "U1") (pin "56") (pinfunction "PB4_56") (pintype "passive"))
      (node (ref "ZMIN") (pin "1") (pinfunction "1_1") (pintype "passive"))
    )
    (net (code "52") (name "/Z_DIR") (class "Default")
      (node (ref "R29") (pin "1") (pinfunction "1_1") (pintype "passive"))
      (node (ref "U1") (pin "28") (pinfunction "PB2_28") (pintype "passive"))
      (node (ref "U6") (pin "8") (pinfunction "DIR_8") (pintype "passive"))
    )
    (net (code "53") (name "/Z_STP") (class "Default")
      (node (ref "U1") (pin "59") (pinfunction "PB7_59") (pintype "passive"))
      (node (ref "U6") (pin "7") (pinfunction "STP_7") (pintype "passive"))
    )
    (net (code "54") (name "GND") (class "Default")
      (node (ref "+3.3V") (pin "1") (pinfunction "1_1") (pintype "passive"))
      (node (ref "+5V") (pin "1") (pinfunction "1_1") (pintype "passive"))
      (node (ref "BLTOUCH1") (pin "1") (pinfunction "1_1") (pintype "passive"))
      (node (ref "BLTOUCH2") (pin "1") (pinfunction "1_1") (pintype "passive"))
      (node (ref "BOOT0") (pin "1") (pinfunction "P$1_1") (pintype "passive"))
      (node (ref "C1") (pin "2") (pinfunction "2_2") (pintype "passive"))
      (node (ref "C10") (pin "1") (pinfunction "1_1") (pintype "passive"))
      (node (ref "C11") (pin "2") (pinfunction "2_2") (pintype "passive"))
      (node (ref "C12") (pin "2") (pinfunction "2_2") (pintype "passive"))
      (node (ref "C13") (pin "2") (pinfunction "2_2") (pintype "passive"))
      (node (ref "C14") (pin "2") (pinfunction "2_2") (pintype "passive"))
      (node (ref "C15") (pin "2") (pinfunction "2_2") (pintype "passive"))
      (node (ref "C16") (pin "2") (pinfunction "2_2") (pintype "passive"))
      (node (ref "C17") (pin "2") (pinfunction "2_2") (pintype "passive"))
      (node (ref "C18") (pin "1") (pinfunction "1_1") (pintype "passive"))
      (node (ref "C19") (pin "1") (pinfunction "1_1") (pintype "passive"))
      (node (ref "C2") (pin "2") (pinfunction "2_2") (pintype "passive"))
      (node (ref "C20") (pin "2") (pinfunction "2_2") (pintype "passive"))
      (node (ref "C21") (pin "2") (pinfunction "2_2") (pintype "passive"))
      (node (ref "C22") (pin "1") (pinfunction "1_1") (pintype "passive"))
      (node (ref "C23") (pin "2") (pinfunction "2_2") (pintype "passive"))
      (node (ref "C24") (pin "2") (pinfunction "2_2") (pintype "passive"))
      (node (ref "C25") (pin "2") (pinfunction "2_2") (pintype "passive"))
      (node (ref "C26") (pin "2") (pinfunction "2_2") (pintype "passive"))
      (node (ref "C27") (pin "2") (pinfunction "2_2") (pintype "passive"))
      (node (ref "C28") (pin "2") (pinfunction "2_2") (pintype "passive"))
      (node (ref "C3") (pin "2") (pinfunction "2_2") (pintype "passive"))
      (node (ref "C31") (pin "2") (pinfunction "2_2") (pintype "passive"))
      (node (ref "C32") (pin "2") (pinfunction "2_2") (pintype "passive"))
      (node (ref "C33") (pin "1") (pinfunction "1_1") (pintype "passive"))
      (node (ref "C34") (pin "2") (pinfunction "2_2") (pintype "passive"))
      (node (ref "C35") (pin "2") (pinfunction "2_2") (pintype "passive"))
      (node (ref "C4") (pin "2") (pinfunction "2_2") (pintype "passive"))
      (node (ref "C5") (pin "2") (pinfunction "2_2") (pintype "passive"))
      (node (ref "C6") (pin "2") (pinfunction "2_2") (pintype "passive"))
      (node (ref "C7") (pin "2") (pinfunction "2_2") (pintype "passive"))
      (node (ref "C8") (pin "2") (pinfunction "2_2") (pintype "passive"))
      (node (ref "C9") (pin "1") (pinfunction "1_1") (pintype "passive"))
      (node (ref "D1") (pin "1") (pinfunction "A_1") (pintype "passive"))
      (node (ref "EXP1") (pin "9") (pinfunction "9_9") (pintype "passive"))
      (node (ref "EXP2") (pin "9") (pinfunction "9_9") (pintype "passive"))
      (node (ref "FAN2") (pin "1") (pinfunction "1_1") (pintype "passive"))
      (node (ref "FILAMENT") (pin "2") (pinfunction "2_2") (pintype "passive"))
      (node (ref "I2C") (pin "2") (pinfunction "2_2") (pintype "passive"))
      (node (ref "J1") (pin "6") (pinfunction "VSS_6") (pintype "passive"))
      (node (ref "J1") (pin "G1") (pinfunction "G1_G1") (pintype "passive"))
      (node (ref "J1") (pin "G2") (pinfunction "G2_G2") (pintype "passive"))
      (node (ref "J1") (pin "G3") (pinfunction "G3_G3") (pintype "passive"))
      (node (ref "J1") (pin "G4") (pinfunction "G4_G4") (pintype "passive"))
      (node (ref "LED5") (pin "2") (pinfunction "C_2") (pintype "passive"))
      (node (ref "MICROSTEPS") (pin "1") (pinfunction "A1_1") (pintype "passive"))
      (node (ref "MICROSTEPS") (pin "2") (pinfunction "A2_2") (pintype "passive"))
      (node (ref "MICROSTEPS") (pin "3") (pinfunction "A3_3") (pintype "passive"))
      (node (ref "POWER") (pin "1") (pinfunction "1_1") (pintype "passive"))
      (node (ref "Q1") (pin "3") (pinfunction "S_3") (pintype "passive"))
      (node (ref "Q2") (pin "3") (pinfunction "S_3") (pintype "passive"))
      (node (ref "Q3") (pin "3") (pinfunction "S_3") (pintype "passive"))
      (node (ref "Q5") (pin "3") (pinfunction "S_3") (pintype "passive"))
      (node (ref "R13") (pin "2") (pinfunction "2_2") (pintype "passive"))
      (node (ref "R29") (pin "2") (pinfunction "2_2") (pintype "passive"))
      (node (ref "R4") (pin "2") (pinfunction "2_2") (pintype "passive"))
      (node (ref "R8") (pin "2") (pinfunction "2_2") (pintype "passive"))
      (node (ref "R9") (pin "2") (pinfunction "2_2") (pintype "passive"))
      (node (ref "SW1") (pin "2") (pinfunction "2_2") (pintype "passive"))
      (node (ref "SW1") (pin "4") (pinfunction "4_4") (pintype "passive"))
      (node (ref "SWD") (pin "4") (pinfunction "4_4") (pintype "passive"))
      (node (ref "TBED") (pin "1") (pinfunction "1_1") (pintype "passive"))
      (node (ref "TEXTR1") (pin "1") (pinfunction "1_1") (pintype "passive"))
      (node (ref "TEXTR2") (pin "1") (pinfunction "1_1") (pintype "passive"))
      (node (ref "U1") (pin "12") (pinfunction "VSSA_12") (pintype "passive"))
      (node (ref "U1") (pin "18") (pinfunction "VSS_18") (pintype "passive"))
      (node (ref "U1") (pin "31") (pinfunction "VSS_31") (pintype "passive"))
      (node (ref "U1") (pin "47") (pinfunction "VSS_47") (pintype "passive"))
      (node (ref "U1") (pin "63") (pinfunction "VSS_63") (pintype "passive"))
      (node (ref "U2") (pin "15") (pinfunction "GndM_15") (pintype "passive"))
      (node (ref "U2") (pin "9") (pinfunction "GndL_9") (pintype "passive"))
      (node (ref "U3") (pin "15") (pinfunction "GndM_15") (pintype "passive"))
      (node (ref "U3") (pin "9") (pinfunction "GndL_9") (pintype "passive"))
      (node (ref "U4") (pin "15") (pinfunction "GndM_15") (pintype "passive"))
      (node (ref "U4") (pin "9") (pinfunction "GndL_9") (pintype "passive"))
      (node (ref "U5") (pin "15") (pinfunction "GndM_15") (pintype "passive"))
      (node (ref "U5") (pin "9") (pinfunction "GndL_9") (pintype "passive"))
      (node (ref "U6") (pin "15") (pinfunction "GndM_15") (pintype "passive"))
      (node (ref "U6") (pin "9") (pinfunction "GndL_9") (pintype "passive"))
      (node (ref "U7") (pin "3") (pinfunction "GROUND_3") (pintype "passive"))
      (node (ref "U7") (pin "5") (pinfunction "ON/OFF_5") (pintype "passive"))
      (node (ref "U8") (pin "1") (pinfunction "GND_1") (pintype "passive"))
      (node (ref "UART") (pin "2") (pinfunction "2_2") (pintype "passive"))
      (node (ref "USB1") (pin "0") (pinfunction "0_0") (pintype "passive"))
      (node (ref "USB1") (pin "4") (pinfunction "GND_4") (pintype "passive"))
      (node (ref "XMAX") (pin "2") (pinfunction "2_2") (pintype "passive"))
      (node (ref "XMIN") (pin "2") (pinfunction "2_2") (pintype "passive"))
      (node (ref "YMAX") (pin "2") (pinfunction "2_2") (pintype "passive"))
      (node (ref "YMIN") (pin "2") (pinfunction "2_2") (pintype "passive"))
      (node (ref "ZMAX") (pin "2") (pinfunction "2_2") (pintype "passive"))
      (node (ref "ZMIN") (pin "2") (pinfunction "2_2") (pintype "passive"))
    )
    (net (code "55") (name "Net-(BOOT0-P$2)") (class "Default")
      (node (ref "BOOT0") (pin "2") (pinfunction "P$2_2") (pintype "passive"))
      (node (ref "R21") (pin "2") (pinfunction "2_2") (pintype "passive"))
    )
    (net (code "56") (name "Net-(D1-K)") (class "Default")
      (node (ref "D1") (pin "2") (pinfunction "K_2") (pintype "passive"))
      (node (ref "L5") (pin "1") (pinfunction "1_1") (pintype "passive"))
      (node (ref "U7") (pin "2") (pinfunction "OUT_2") (pintype "passive"))
    )
    (net (code "57") (name "Net-(LED1-A)") (class "Default")
      (node (ref "LED1") (pin "1") (pinfunction "A_1") (pintype "passive"))
      (node (ref "R5") (pin "2") (pinfunction "2_2") (pintype "passive"))
    )
    (net (code "58") (name "Net-(LED1-C)") (class "Default")
      (node (ref "HEATBED") (pin "2") (pinfunction "2_2") (pintype "passive"))
      (node (ref "LED1") (pin "2") (pinfunction "C_2") (pintype "passive"))
      (node (ref "Q2") (pin "4") (pinfunction "D_4") (pintype "passive"))
    )
    (net (code "59") (name "Net-(LED2-A)") (class "Default")
      (node (ref "LED2") (pin "1") (pinfunction "A_1") (pintype "passive"))
      (node (ref "R6") (pin "2") (pinfunction "2_2") (pintype "passive"))
    )
    (net (code "60") (name "Net-(LED2-C)") (class "Default")
      (node (ref "EXTRUDER1") (pin "2") (pinfunction "2_2") (pintype "passive"))
      (node (ref "LED2") (pin "2") (pinfunction "C_2") (pintype "passive"))
      (node (ref "Q5") (pin "4") (pinfunction "D_4") (pintype "passive"))
    )
    (net (code "61") (name "Net-(LED3-A)") (class "Default")
      (node (ref "LED3") (pin "1") (pinfunction "A_1") (pintype "passive"))
      (node (ref "R11") (pin "2") (pinfunction "2_2") (pintype "passive"))
    )
    (net (code "62") (name "Net-(LED3-C)") (class "Default")
      (node (ref "EXTRUDER2") (pin "2") (pinfunction "2_2") (pintype "passive"))
      (node (ref "LED3") (pin "2") (pinfunction "C_2") (pintype "passive"))
      (node (ref "Q1") (pin "4") (pinfunction "D_4") (pintype "passive"))
    )
    (net (code "63") (name "Net-(LED4-A)") (class "Default")
      (node (ref "LED4") (pin "1") (pinfunction "A_1") (pintype "passive"))
      (node (ref "R14") (pin "2") (pinfunction "2_2") (pintype "passive"))
    )
    (net (code "64") (name "Net-(LED4-C)") (class "Default")
      (node (ref "FAN1") (pin "1") (pinfunction "1_1") (pintype "passive"))
      (node (ref "LED4") (pin "2") (pinfunction "C_2") (pintype "passive"))
      (node (ref "Q3") (pin "4") (pinfunction "D_4") (pintype "passive"))
    )
    (net (code "65") (name "Net-(LED5-A)") (class "Default")
      (node (ref "LED5") (pin "1") (pinfunction "A_1") (pintype "passive"))
      (node (ref "R24") (pin "2") (pinfunction "2_2") (pintype "passive"))
    )
    (net (code "66") (name "Net-(MICROSTEPS-B1)") (class "Default")
      (node (ref "MICROSTEPS") (pin "6") (pinfunction "B1_6") (pintype "passive"))
      (node (ref "R1") (pin "1") (pinfunction "1_1") (pintype "passive"))
      (node (ref "U2") (pin "2") (pinfunction "M0_2") (pintype "passive"))
      (node (ref "U3") (pin "2") (pinfunction "M0_2") (pintype "passive"))
      (node (ref "U4") (pin "2") (pinfunction "M0_2") (pintype "passive"))
      (node (ref "U5") (pin "2") (pinfunction "M0_2") (pintype "passive"))
      (node (ref "U6") (pin "2") (pinfunction "M0_2") (pintype "passive"))
    )
    (net (code "67") (name "Net-(MICROSTEPS-B2)") (class "Default")
      (node (ref "MICROSTEPS") (pin "5") (pinfunction "B2_5") (pintype "passive"))
      (node (ref "R2") (pin "1") (pinfunction "1_1") (pintype "passive"))
      (node (ref "U2") (pin "3") (pinfunction "M1_3") (pintype "passive"))
      (node (ref "U3") (pin "3") (pinfunction "M1_3") (pintype "passive"))
      (node (ref "U4") (pin "3") (pinfunction "M1_3") (pintype "passive"))
      (node (ref "U5") (pin "3") (pinfunction "M1_3") (pintype "passive"))
      (node (ref "U6") (pin "3") (pinfunction "M1_3") (pintype "passive"))
    )
    (net (code "68") (name "Net-(MICROSTEPS-B3)") (class "Default")
      (node (ref "MICROSTEPS") (pin "4") (pinfunction "B3_4") (pintype "passive"))
      (node (ref "R3") (pin "1") (pinfunction "1_1") (pintype "passive"))
      (node (ref "U2") (pin "4") (pinfunction "M2_4") (pintype "passive"))
      (node (ref "U3") (pin "4") (pinfunction "M2_4") (pintype "passive"))
      (node (ref "U4") (pin "4") (pinfunction "M2_4") (pintype "passive"))
      (node (ref "U5") (pin "4") (pinfunction "M2_4") (pintype "passive"))
      (node (ref "U6") (pin "4") (pinfunction "M2_4") (pintype "passive"))
    )
    (net (code "69") (name "Net-(Q1-G)") (class "Default")
      (node (ref "Q1") (pin "1") (pinfunction "G_1") (pintype "passive"))
      (node (ref "R10") (pin "1") (pinfunction "1_1") (pintype "passive"))
    )
    (net (code "70") (name "Net-(Q2-G)") (class "Default")
      (node (ref "Q2") (pin "1") (pinfunction "G_1") (pintype "passive"))
      (node (ref "R20") (pin "1") (pinfunction "1_1") (pintype "passive"))
    )
    (net (code "71") (name "Net-(Q3-G)") (class "Default")
      (node (ref "Q3") (pin "1") (pinfunction "G_1") (pintype "passive"))
      (node (ref "R12") (pin "1") (pinfunction "1_1") (pintype "passive"))
    )
    (net (code "72") (name "Net-(Q5-G)") (class "Default")
      (node (ref "Q5") (pin "1") (pinfunction "G_1") (pintype "passive"))
      (node (ref "R7") (pin "1") (pinfunction "1_1") (pintype "passive"))
    )
    (net (code "73") (name "Net-(U1-BOOT0)") (class "Default")
      (node (ref "R21") (pin "1") (pinfunction "1_1") (pintype "passive"))
      (node (ref "U1") (pin "60") (pinfunction "BOOT0_60") (pintype "passive"))
    )
    (net (code "74") (name "Net-(U1-PD0{slash}OSC{slash}IN)") (class "Default")
      (node (ref "C11") (pin "1") (pinfunction "1_1") (pintype "passive"))
      (node (ref "U1") (pin "5") (pinfunction "PD0/OSC/IN_5") (pintype "passive"))
      (node (ref "Y1") (pin "2") (pinfunction "2_2") (pintype "passive"))
    )
    (net (code "75") (name "Net-(U1-PD1{slash}OSC{slash}OUT)") (class "Default")
      (node (ref "C20") (pin "1") (pinfunction "1_1") (pintype "passive"))
      (node (ref "U1") (pin "6") (pinfunction "PD1/OSC/OUT_6") (pintype "passive"))
      (node (ref "Y1") (pin "1") (pinfunction "1_1") (pintype "passive"))
    )
    (net (code "76") (name "Net-(U1-VDDA)") (class "Default")
      (node (ref "C21") (pin "1") (pinfunction "1_1") (pintype "passive"))
      (node (ref "L1") (pin "2") (pinfunction "2_2") (pintype "passive"))
      (node (ref "U1") (pin "13") (pinfunction "VDDA_13") (pintype "passive"))
    )
    (net (code "77") (name "Net-(U2-A1)") (class "Default")
      (node (ref "E1") (pin "3") (pinfunction "3_3") (pintype "passive"))
      (node (ref "U2") (pin "12") (pinfunction "A1_12") (pintype "passive"))
    )
    (net (code "78") (name "Net-(U2-A2)") (class "Default")
      (node (ref "E1") (pin "4") (pinfunction "4_4") (pintype "passive"))
      (node (ref "U2") (pin "11") (pinfunction "A2_11") (pintype "passive"))
    )
    (net (code "79") (name "Net-(U2-B1)") (class "Default")
      (node (ref "E1") (pin "2") (pinfunction "2_2") (pintype "passive"))
      (node (ref "U2") (pin "13") (pinfunction "B1_13") (pintype "passive"))
    )
    (net (code "80") (name "Net-(U2-B2)") (class "Default")
      (node (ref "E1") (pin "1") (pinfunction "1_1") (pintype "passive"))
      (node (ref "U2") (pin "14") (pinfunction "B2_14") (pintype "passive"))
    )
    (net (code "81") (name "Net-(U2-RST)") (class "Default")
      (node (ref "U2") (pin "5") (pinfunction "RST_5") (pintype "passive"))
      (node (ref "U2") (pin "6") (pinfunction "SLP_6") (pintype "passive"))
    )
    (net (code "82") (name "Net-(U3-A1)") (class "Default")
      (node (ref "E2") (pin "3") (pinfunction "3_3") (pintype "passive"))
      (node (ref "U3") (pin "12") (pinfunction "A1_12") (pintype "passive"))
    )
    (net (code "83") (name "Net-(U3-A2)") (class "Default")
      (node (ref "E2") (pin "4") (pinfunction "4_4") (pintype "passive"))
      (node (ref "U3") (pin "11") (pinfunction "A2_11") (pintype "passive"))
    )
    (net (code "84") (name "Net-(U3-B1)") (class "Default")
      (node (ref "E2") (pin "2") (pinfunction "2_2") (pintype "passive"))
      (node (ref "U3") (pin "13") (pinfunction "B1_13") (pintype "passive"))
    )
    (net (code "85") (name "Net-(U3-B2)") (class "Default")
      (node (ref "E2") (pin "1") (pinfunction "1_1") (pintype "passive"))
      (node (ref "U3") (pin "14") (pinfunction "B2_14") (pintype "passive"))
    )
    (net (code "86") (name "Net-(U3-RST)") (class "Default")
      (node (ref "U3") (pin "5") (pinfunction "RST_5") (pintype "passive"))
      (node (ref "U3") (pin "6") (pinfunction "SLP_6") (pintype "passive"))
    )
    (net (code "87") (name "Net-(U4-A1)") (class "Default")
      (node (ref "U4") (pin "12") (pinfunction "A1_12") (pintype "passive"))
      (node (ref "X") (pin "3") (pinfunction "3_3") (pintype "passive"))
    )
    (net (code "88") (name "Net-(U4-A2)") (class "Default")
      (node (ref "U4") (pin "11") (pinfunction "A2_11") (pintype "passive"))
      (node (ref "X") (pin "4") (pinfunction "4_4") (pintype "passive"))
    )
    (net (code "89") (name "Net-(U4-B1)") (class "Default")
      (node (ref "U4") (pin "13") (pinfunction "B1_13") (pintype "passive"))
      (node (ref "X") (pin "2") (pinfunction "2_2") (pintype "passive"))
    )
    (net (code "90") (name "Net-(U4-B2)") (class "Default")
      (node (ref "U4") (pin "14") (pinfunction "B2_14") (pintype "passive"))
      (node (ref "X") (pin "1") (pinfunction "1_1") (pintype "passive"))
    )
    (net (code "91") (name "Net-(U4-RST)") (class "Default")
      (node (ref "U4") (pin "5") (pinfunction "RST_5") (pintype "passive"))
      (node (ref "U4") (pin "6") (pinfunction "SLP_6") (pintype "passive"))
    )
    (net (code "92") (name "Net-(U5-A1)") (class "Default")
      (node (ref "U5") (pin "12") (pinfunction "A1_12") (pintype "passive"))
      (node (ref "Y") (pin "3") (pinfunction "3_3") (pintype "passive"))
    )
    (net (code "93") (name "Net-(U5-A2)") (class "Default")
      (node (ref "U5") (pin "11") (pinfunction "A2_11") (pintype "passive"))
      (node (ref "Y") (pin "4") (pinfunction "4_4") (pintype "passive"))
    )
    (net (code "94") (name "Net-(U5-B1)") (class "Default")
      (node (ref "U5") (pin "13") (pinfunction "B1_13") (pintype "passive"))
      (node (ref "Y") (pin "2") (pinfunction "2_2") (pintype "passive"))
    )
    (net (code "95") (name "Net-(U5-B2)") (class "Default")
      (node (ref "U5") (pin "14") (pinfunction "B2_14") (pintype "passive"))
      (node (ref "Y") (pin "1") (pinfunction "1_1") (pintype "passive"))
    )
    (net (code "96") (name "Net-(U5-RST)") (class "Default")
      (node (ref "U5") (pin "5") (pinfunction "RST_5") (pintype "passive"))
      (node (ref "U5") (pin "6") (pinfunction "SLP_6") (pintype "passive"))
    )
    (net (code "97") (name "Net-(U6-A1)") (class "Default")
      (node (ref "U6") (pin "12") (pinfunction "A1_12") (pintype "passive"))
      (node (ref "Z") (pin "3") (pinfunction "3_3") (pintype "passive"))
      (node (ref "Z1") (pin "3") (pinfunction "3_3") (pintype "passive"))
    )
    (net (code "98") (name "Net-(U6-A2)") (class "Default")
      (node (ref "U6") (pin "11") (pinfunction "A2_11") (pintype "passive"))
      (node (ref "Z") (pin "4") (pinfunction "4_4") (pintype "passive"))
      (node (ref "Z2") (pin "4") (pinfunction "4_4") (pintype "passive"))
    )
    (net (code "99") (name "Net-(U6-B1)") (class "Default")
      (node (ref "U6") (pin "13") (pinfunction "B1_13") (pintype "passive"))
      (node (ref "Z") (pin "2") (pinfunction "2_2") (pintype "passive"))
      (node (ref "Z2") (pin "2") (pinfunction "2_2") (pintype "passive"))
    )
    (net (code "100") (name "Net-(U6-B2)") (class "Default")
      (node (ref "U6") (pin "14") (pinfunction "B2_14") (pintype "passive"))
      (node (ref "Z") (pin "1") (pinfunction "1_1") (pintype "passive"))
      (node (ref "Z1") (pin "1") (pinfunction "1_1") (pintype "passive"))
    )
    (net (code "101") (name "Net-(U6-RST)") (class "Default")
      (node (ref "U6") (pin "5") (pinfunction "RST_5") (pintype "passive"))
      (node (ref "U6") (pin "6") (pinfunction "SLP_6") (pintype "passive"))
    )
    (net (code "102") (name "Net-(USB1-D+)") (class "Default")
      (node (ref "R18") (pin "2") (pinfunction "2_2") (pintype "passive"))
      (node (ref "R25") (pin "2") (pinfunction "2_2") (pintype "passive"))
      (node (ref "USB1") (pin "3") (pinfunction "D+_3") (pintype "passive"))
    )
    (net (code "103") (name "Net-(USB1-D-)") (class "Default")
      (node (ref "R22") (pin "2") (pinfunction "2_2") (pintype "passive"))
      (node (ref "USB1") (pin "2") (pinfunction "D-_2") (pintype "passive"))
    )
    (net (code "104") (name "Net-(Z1-Pad2)") (class "Default")
      (node (ref "Z1") (pin "2") (pinfunction "2_2") (pintype "passive"))
      (node (ref "Z2") (pin "1") (pinfunction "1_1") (pintype "passive"))
    )
    (net (code "105") (name "Net-(Z1-Pad4)") (class "Default")
      (node (ref "Z1") (pin "4") (pinfunction "4_4") (pintype "passive"))
      (node (ref "Z2") (pin "3") (pinfunction "3_3") (pintype "passive"))
    )
    (net (code "106") (name "VCC") (class "Default")
      (node (ref "+3.3V") (pin "2") (pinfunction "2_2") (pintype "passive"))
      (node (ref "BOOT0") (pin "3") (pinfunction "P$3_3") (pintype "passive"))
      (node (ref "C12") (pin "1") (pinfunction "1_1") (pintype "passive"))
      (node (ref "C13") (pin "1") (pinfunction "1_1") (pintype "passive"))
      (node (ref "C14") (pin "1") (pinfunction "1_1") (pintype "passive"))
      (node (ref "C15") (pin "1") (pinfunction "1_1") (pintype "passive"))
      (node (ref "C16") (pin "1") (pinfunction "1_1") (pintype "passive"))
      (node (ref "C19") (pin "2") (pinfunction "2_2") (pintype "passive"))
      (node (ref "C23") (pin "1") (pinfunction "1_1") (pintype "passive"))
      (node (ref "C24") (pin "1") (pinfunction "1_1") (pintype "passive"))
      (node (ref "C25") (pin "1") (pinfunction "1_1") (pintype "passive"))
      (node (ref "C26") (pin "1") (pinfunction "1_1") (pintype "passive"))
      (node (ref "C27") (pin "1") (pinfunction "1_1") (pintype "passive"))
      (node (ref "D5") (pin "2") (pinfunction "K_2") (pintype "passive"))
      (node (ref "I2C") (pin "1") (pinfunction "1_1") (pintype "passive"))
      (node (ref "J1") (pin "4") (pinfunction "VDD_4") (pintype "passive"))
      (node (ref "L1") (pin "1") (pinfunction "1_1") (pintype "passive"))
      (node (ref "R1") (pin "2") (pinfunction "2_2") (pintype "passive"))
      (node (ref "R15") (pin "2") (pinfunction "2_2") (pintype "passive"))
      (node (ref "R16") (pin "2") (pinfunction "2_2") (pintype "passive"))
      (node (ref "R17") (pin "2") (pinfunction "2_2") (pintype "passive"))
      (node (ref "R19") (pin "2") (pinfunction "2_2") (pintype "passive"))
      (node (ref "R2") (pin "2") (pinfunction "2_2") (pintype "passive"))
      (node (ref "R23") (pin "1") (pinfunction "1_1") (pintype "passive"))
      (node (ref "R25") (pin "1") (pinfunction "1_1") (pintype "passive"))
      (node (ref "R26") (pin "1") (pinfunction "1_1") (pintype "passive"))
      (node (ref "R27") (pin "2") (pinfunction "2_2") (pintype "passive"))
      (node (ref "R28") (pin "2") (pinfunction "2_2") (pintype "passive"))
      (node (ref "R3") (pin "2") (pinfunction "2_2") (pintype "passive"))
      (node (ref "R30") (pin "2") (pinfunction "2_2") (pintype "passive"))
      (node (ref "R31") (pin "2") (pinfunction "2_2") (pintype "passive"))
      (node (ref "R32") (pin "2") (pinfunction "2_2") (pintype "passive"))
      (node (ref "SWD") (pin "1") (pinfunction "1_1") (pintype "passive"))
      (node (ref "U1") (pin "1") (pinfunction "VBAT_1") (pintype "passive"))
      (node (ref "U1") (pin "19") (pinfunction "VDD_19") (pintype "passive"))
      (node (ref "U1") (pin "32") (pinfunction "VDD_32") (pintype "passive"))
      (node (ref "U1") (pin "48") (pinfunction "VDD_48") (pintype "passive"))
      (node (ref "U1") (pin "64") (pinfunction "VDD_64") (pintype "passive"))
      (node (ref "U2") (pin "10") (pinfunction "FLT_10") (pintype "passive"))
      (node (ref "U3") (pin "10") (pinfunction "FLT_10") (pintype "passive"))
      (node (ref "U4") (pin "10") (pinfunction "FLT_10") (pintype "passive"))
      (node (ref "U5") (pin "10") (pinfunction "FLT_10") (pintype "passive"))
      (node (ref "U6") (pin "10") (pinfunction "FLT_10") (pintype "passive"))
      (node (ref "U8") (pin "2") (pinfunction "Out_2") (pintype "passive"))
      (node (ref "UART") (pin "1") (pinfunction "1_1") (pintype "passive"))
    )
    (net (code "107") (name "unconnected-(J1-DATA1-Pad8)") (class "Default")
      (node (ref "J1") (pin "8") (pinfunction "DATA1_8") (pintype "passive"))
    )
    (net (code "108") (name "unconnected-(J1-DATA2-Pad1)") (class "Default")
      (node (ref "J1") (pin "1") (pinfunction "DATA2_1") (pintype "passive"))
    )
  )
)
